# modul_frequency.net
KiCad netlist of a schematic drawn in EAGLE
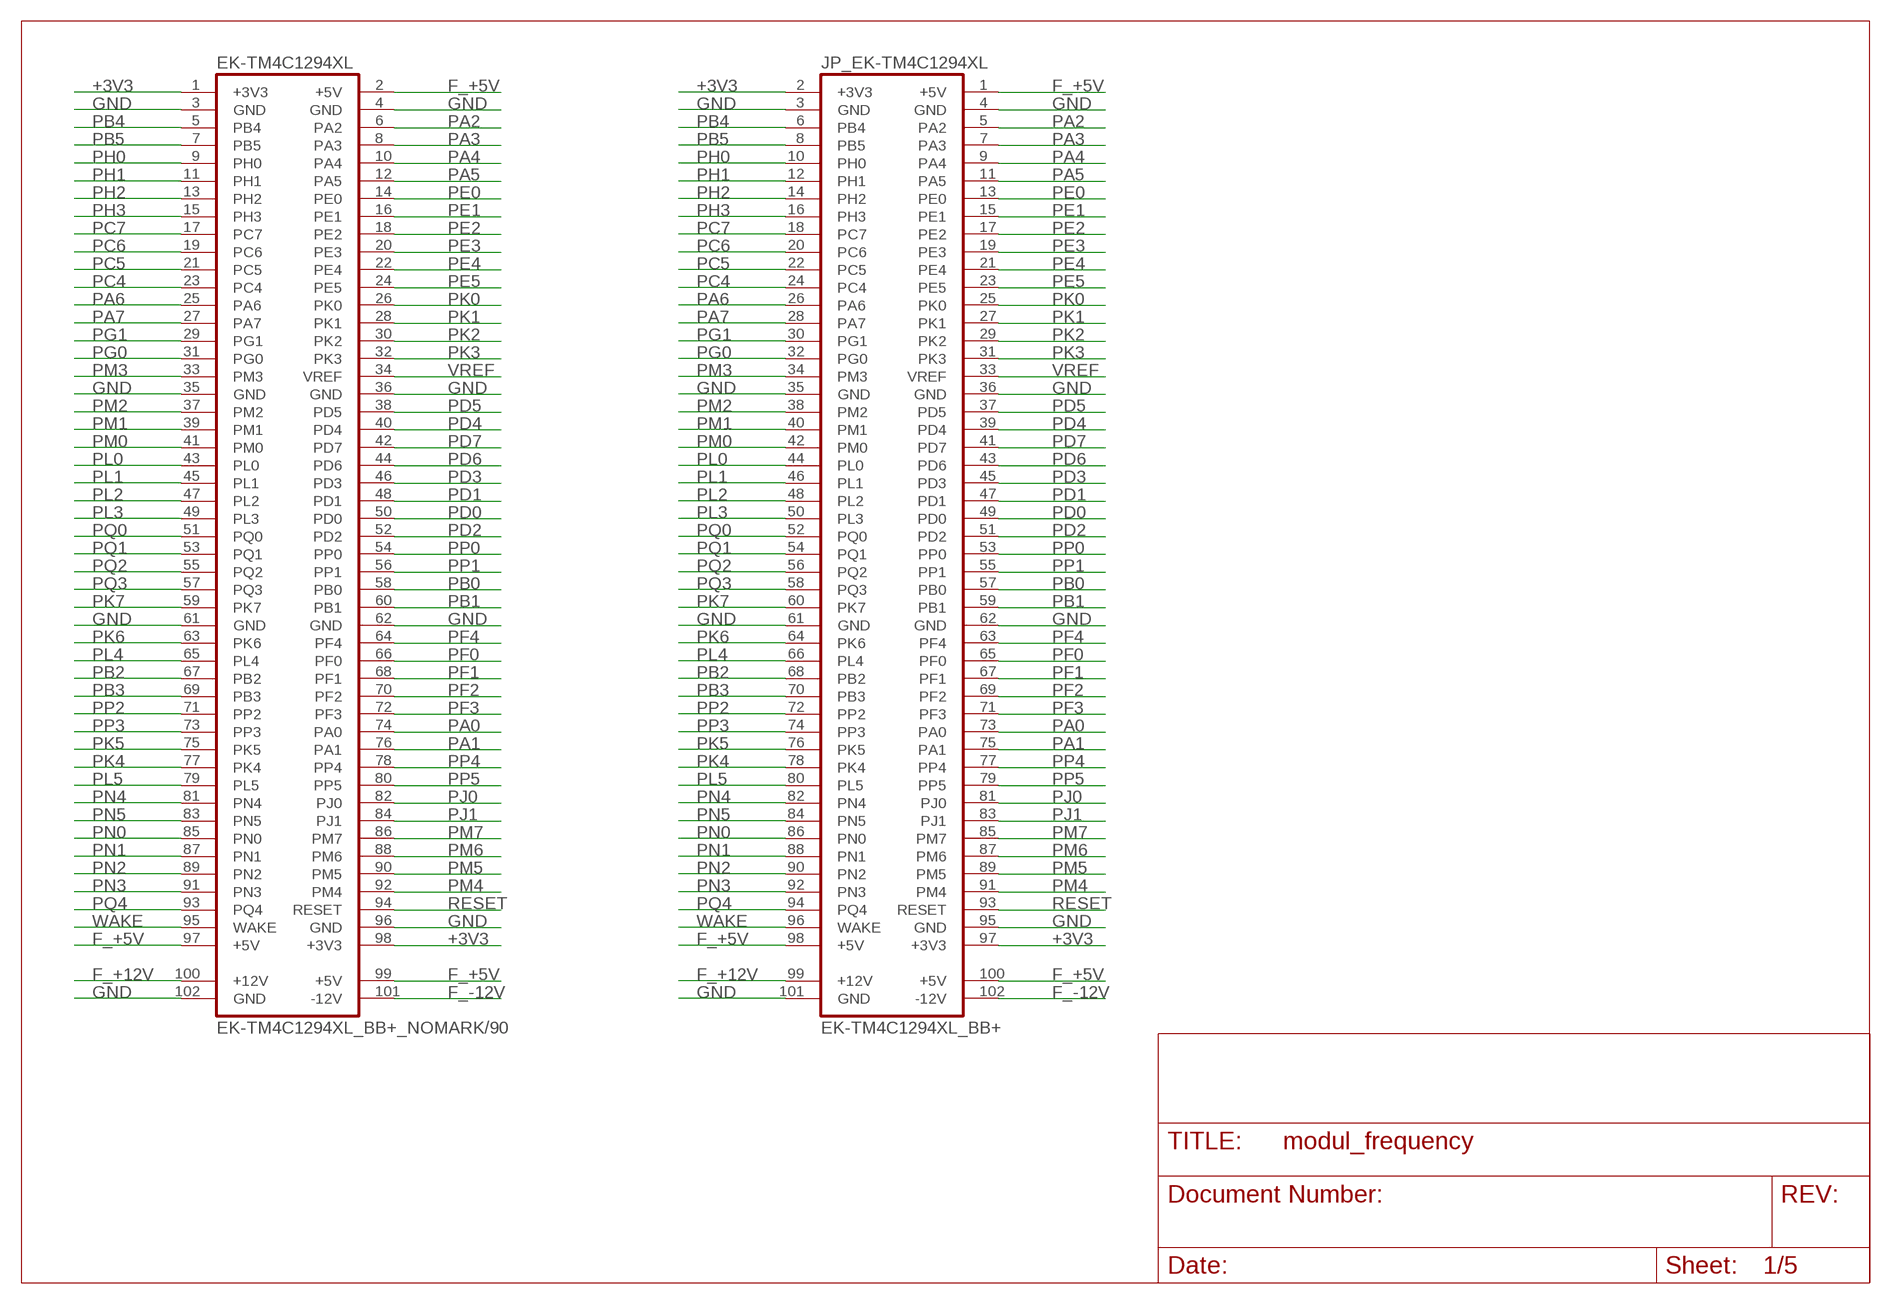
[diagram p0: schematic, sheet 1]
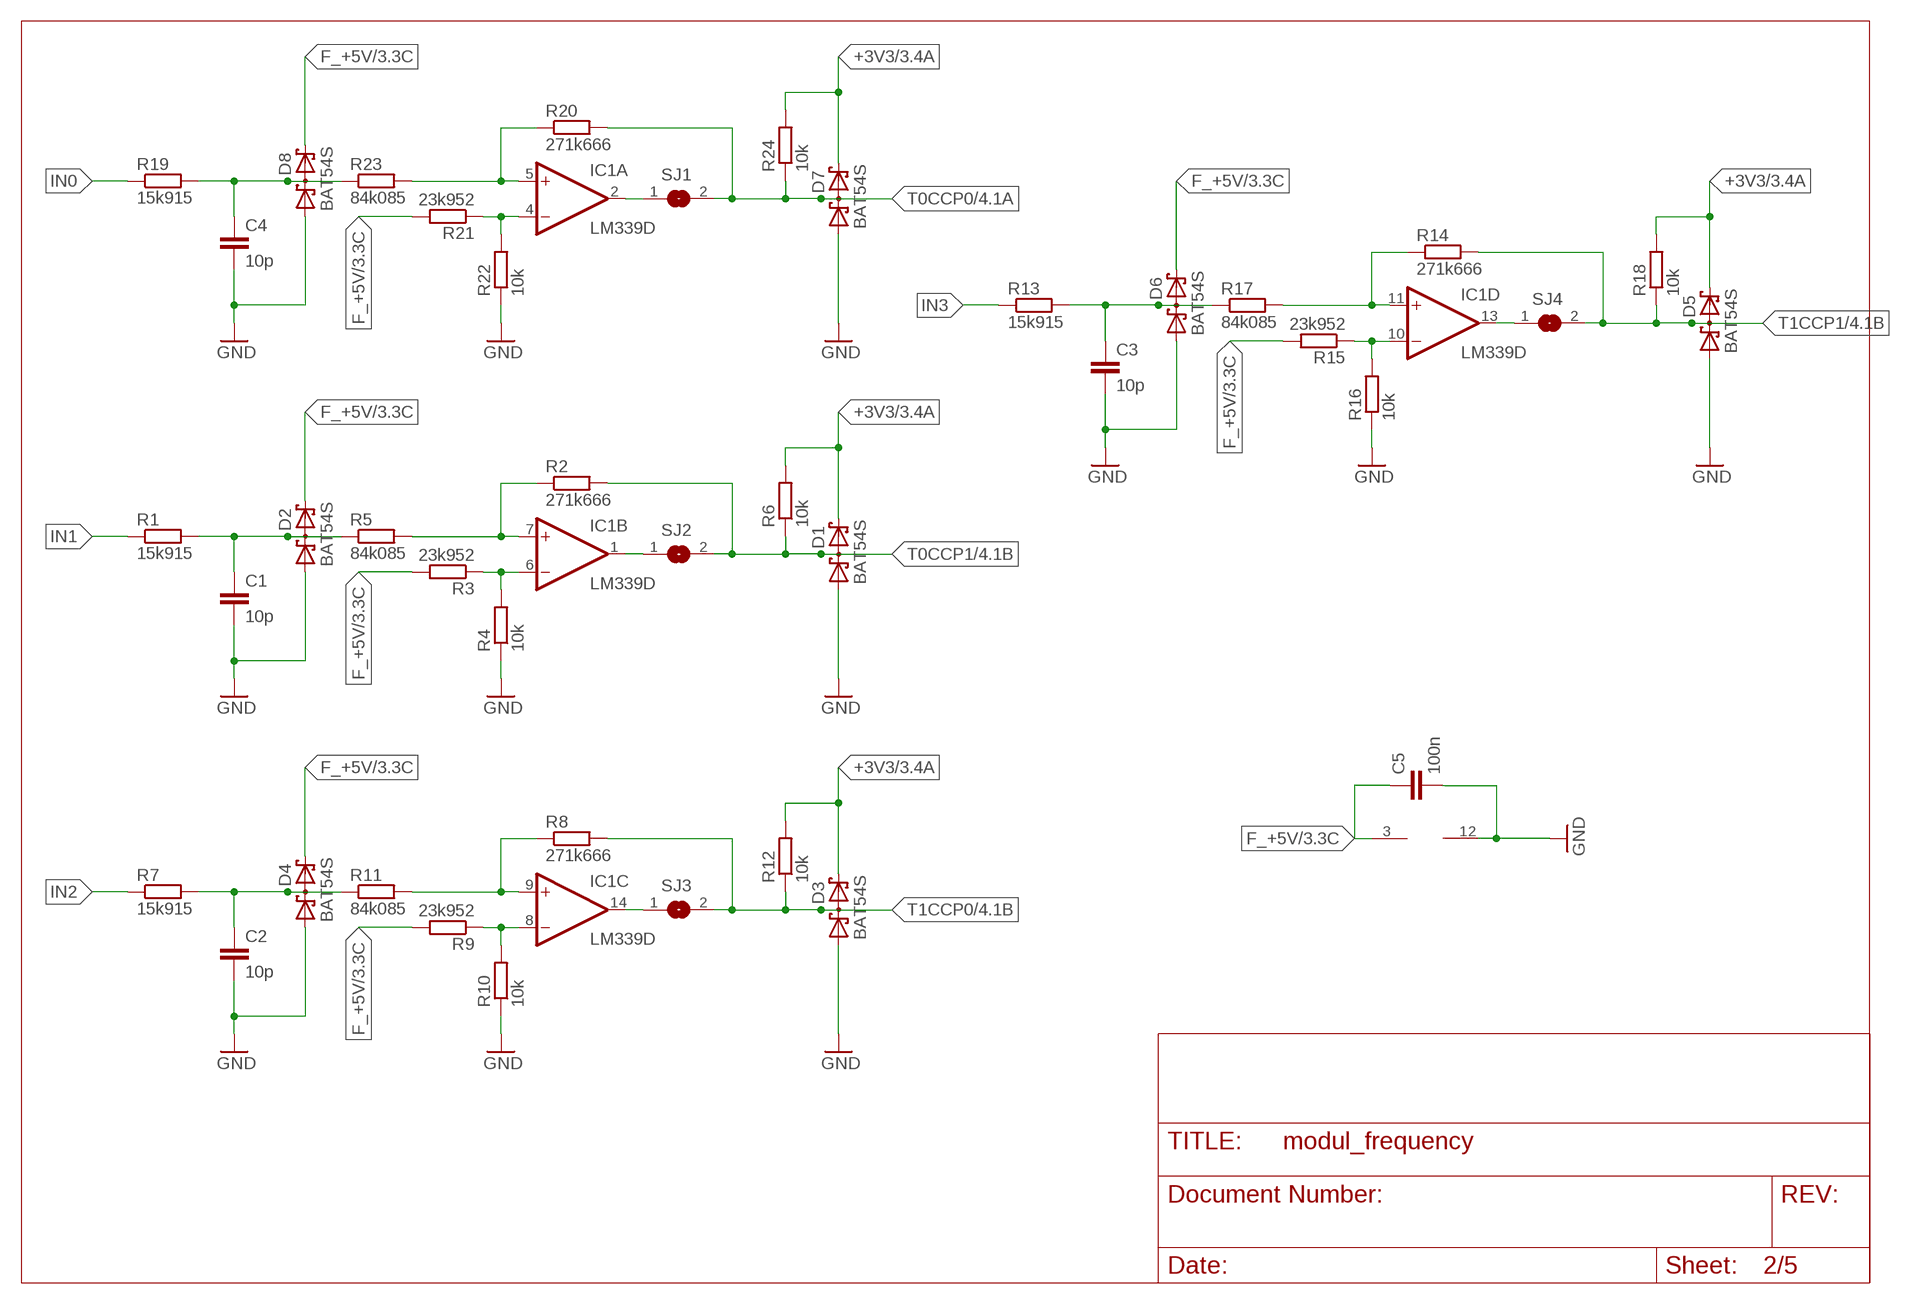
[diagram p1: schematic, sheet 2]
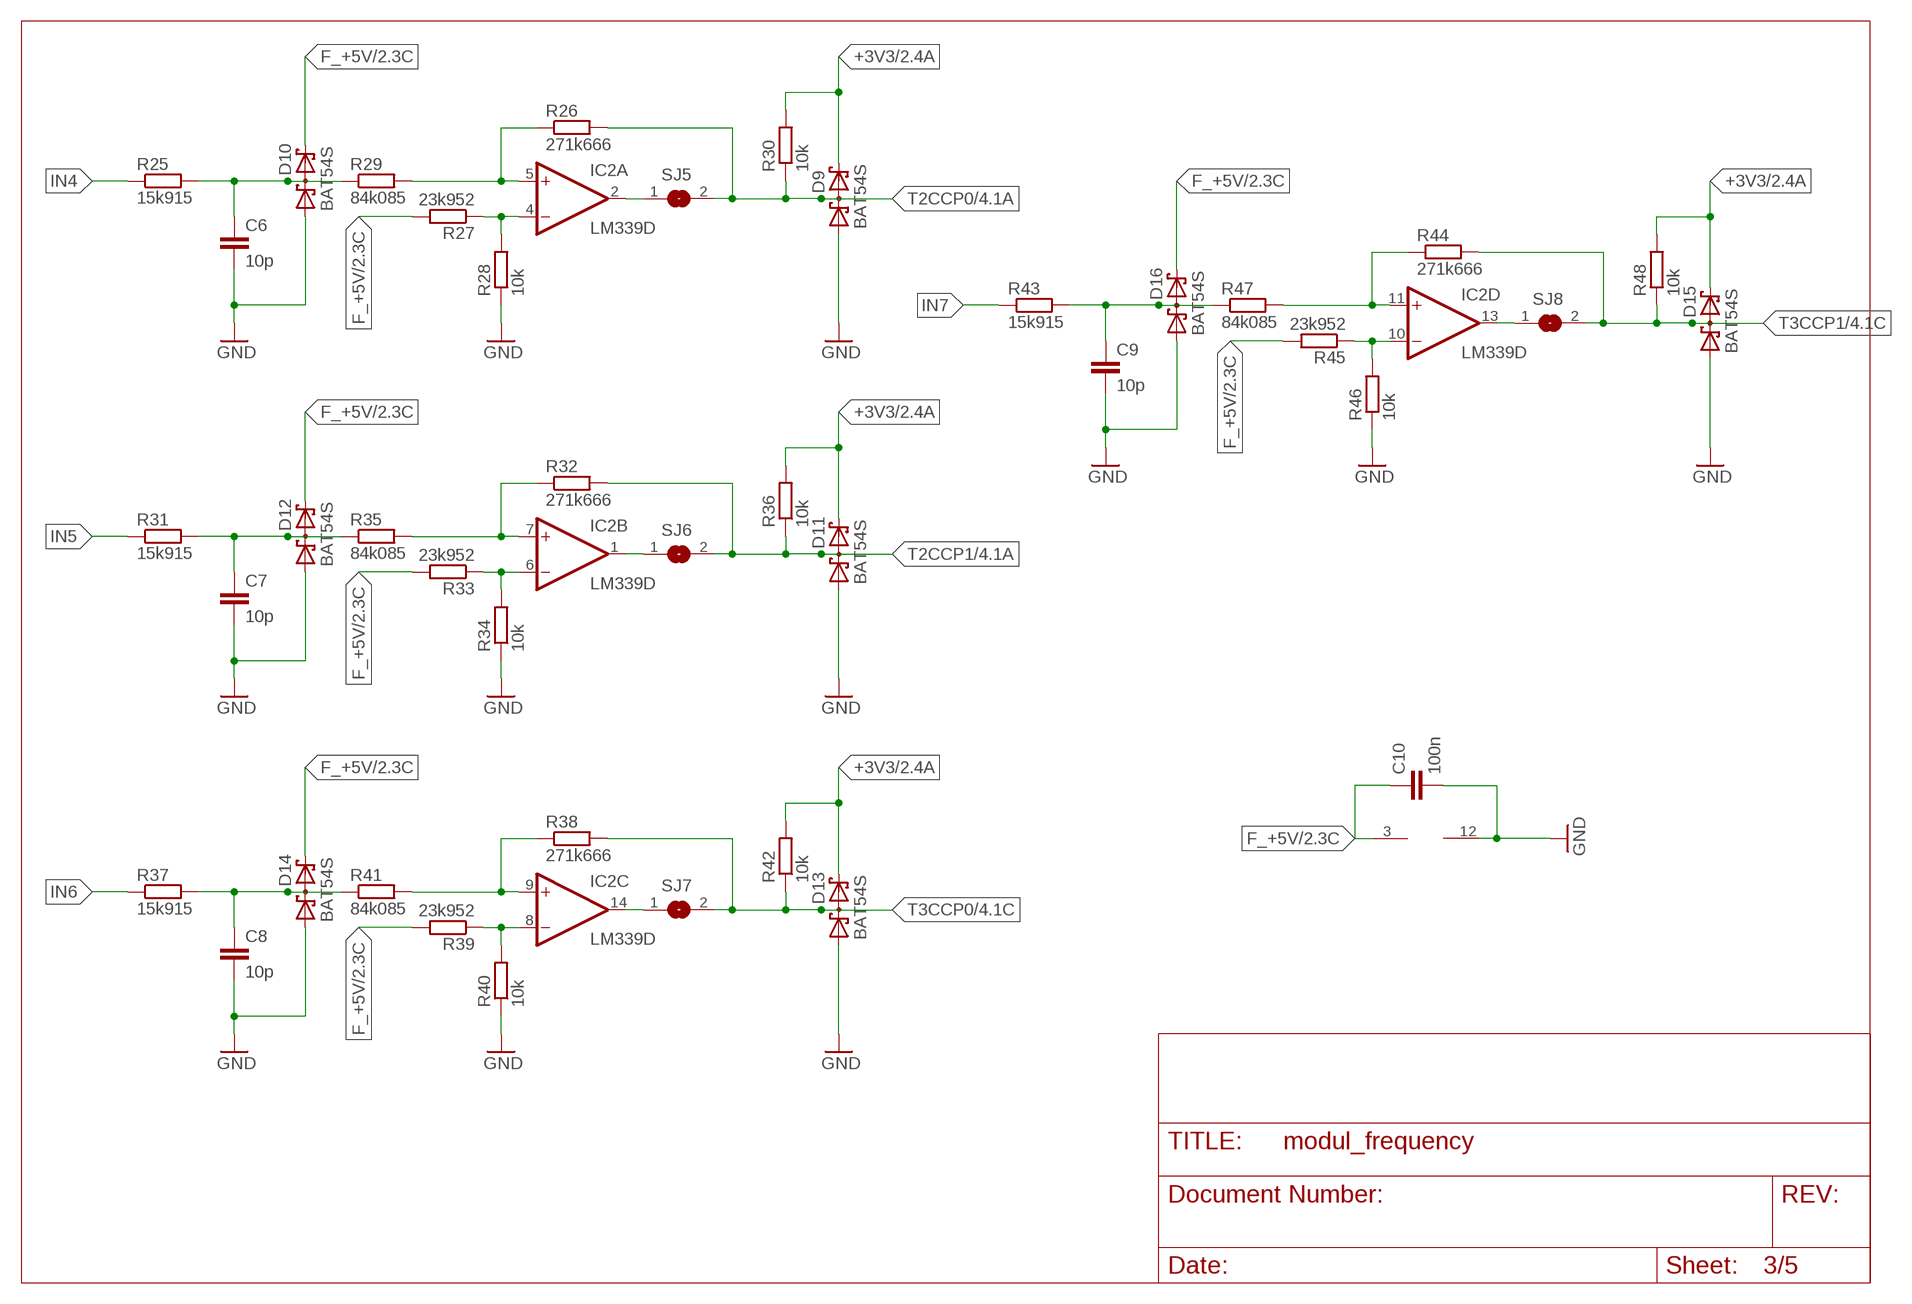
[diagram p2: schematic, sheet 3]
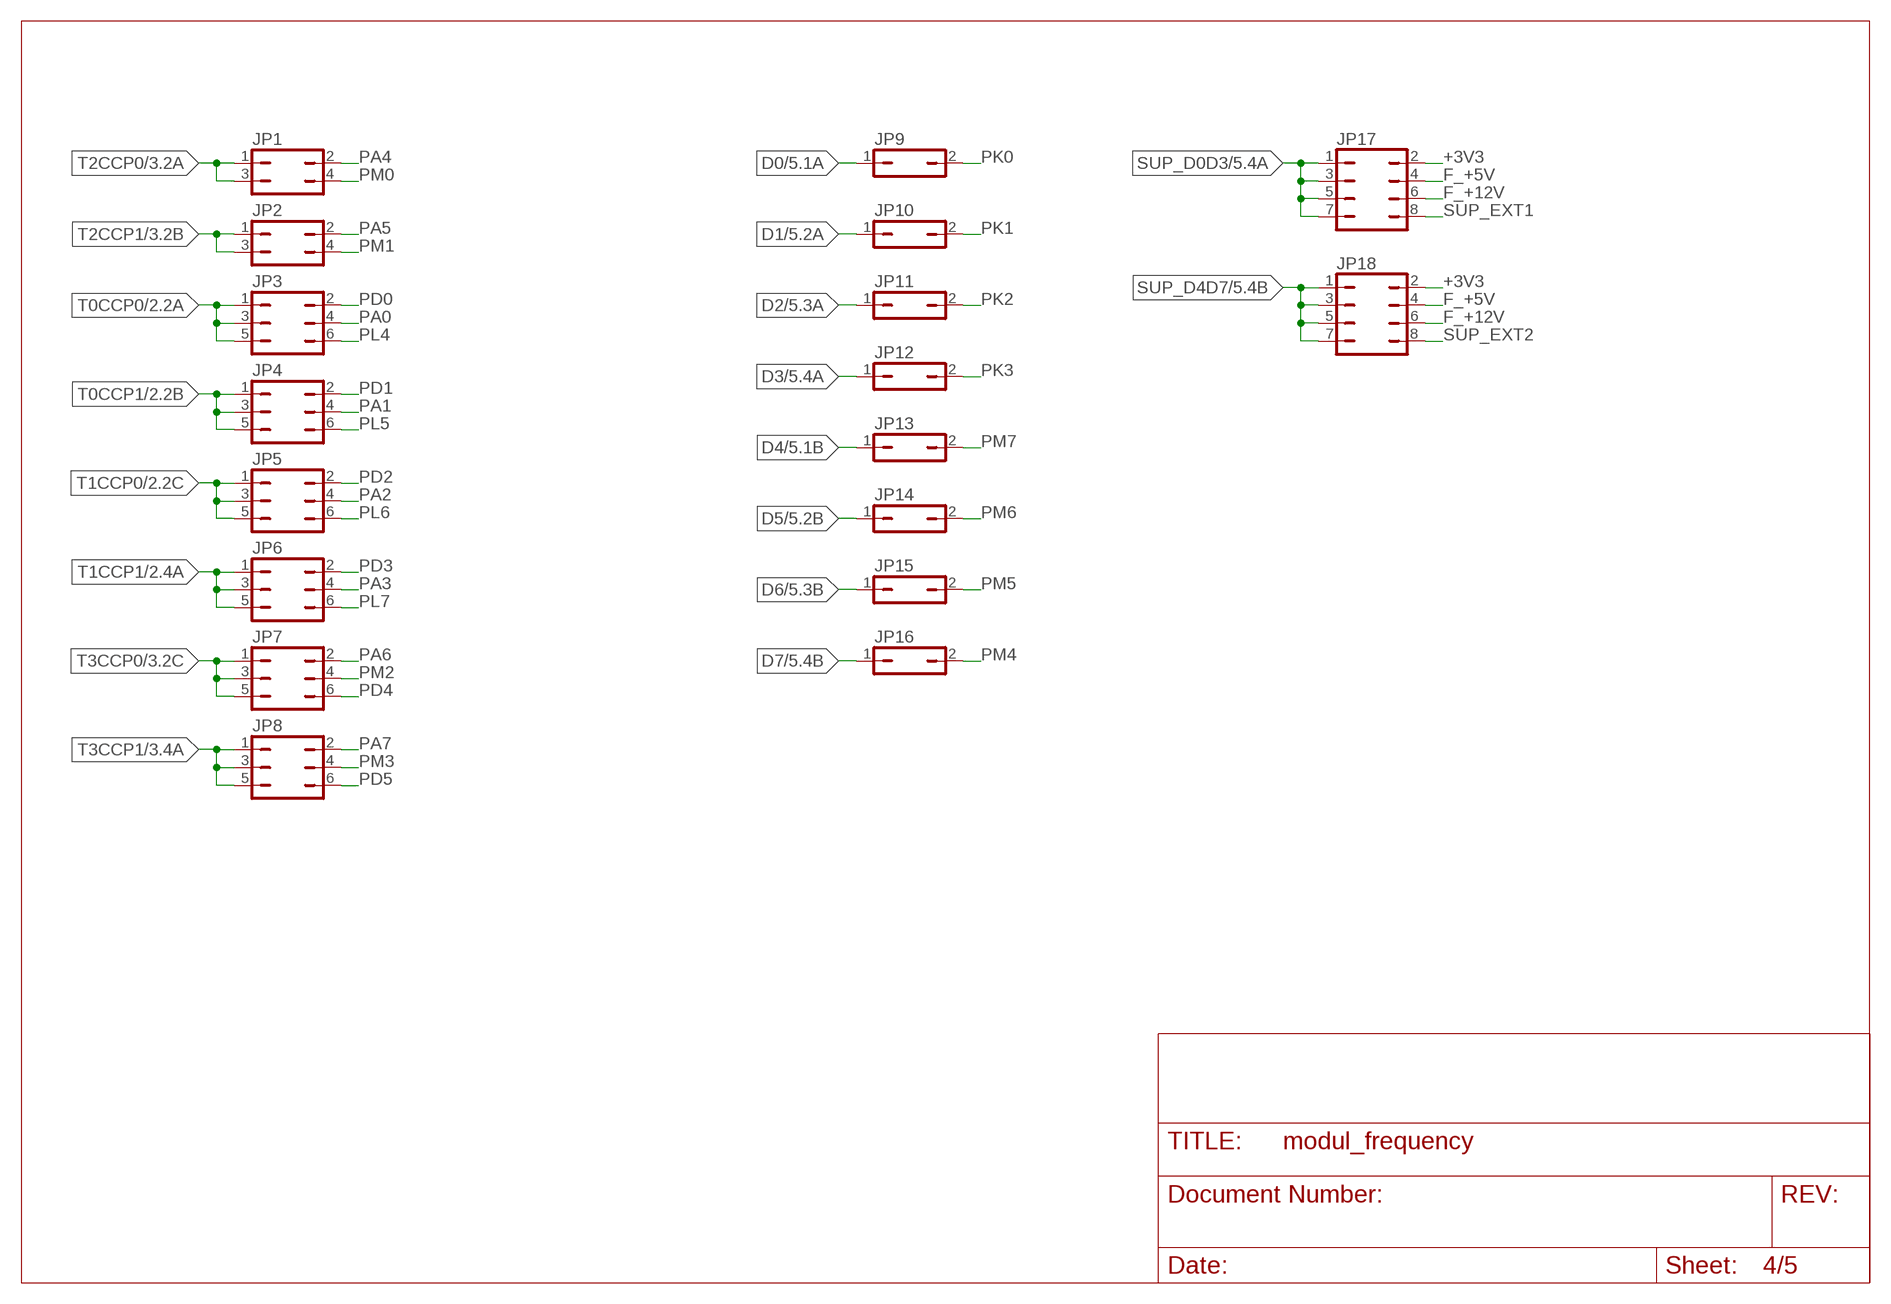
[diagram p3: schematic, sheet 4]
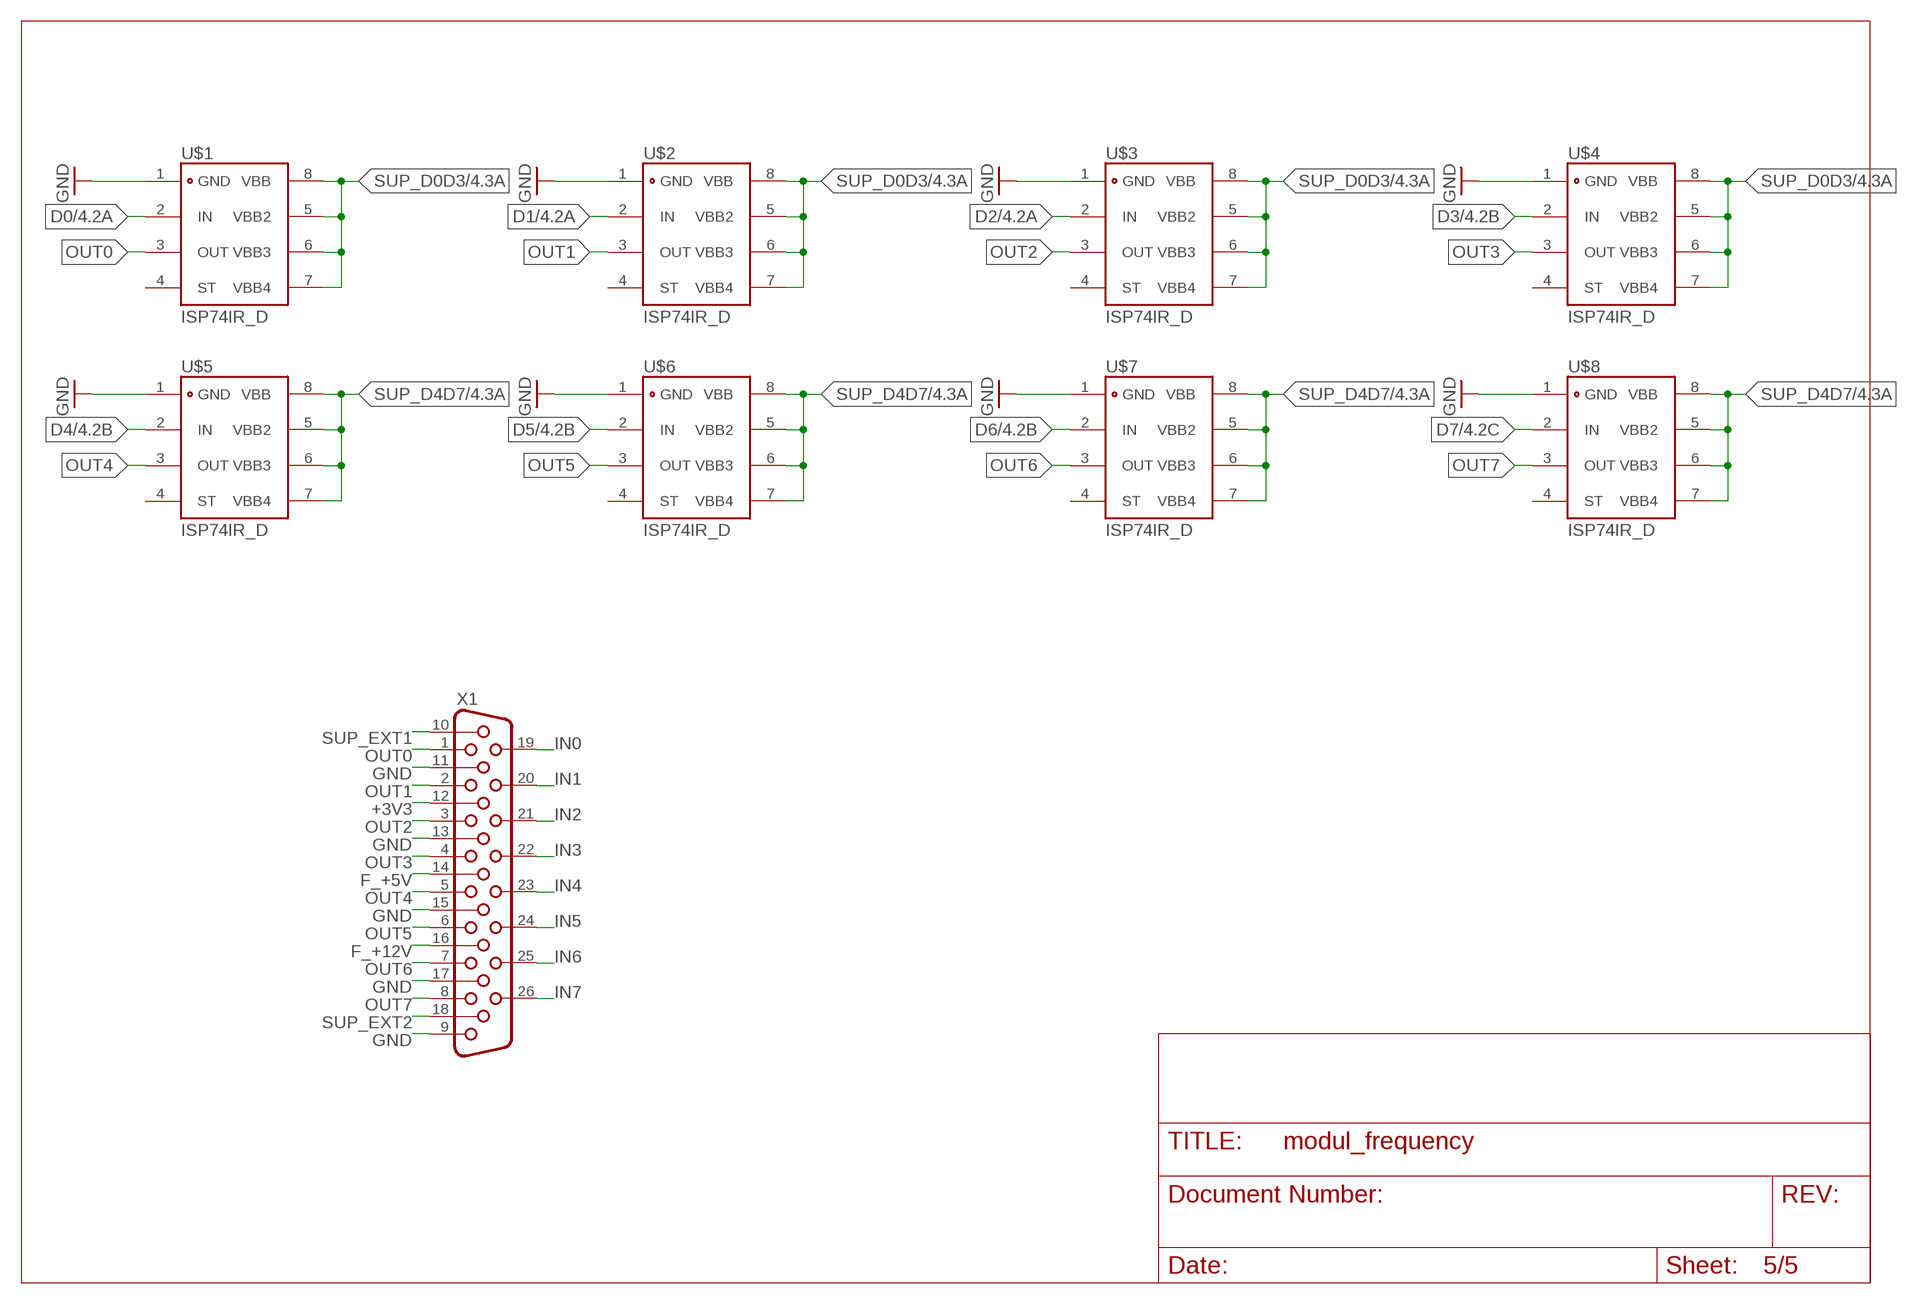
[diagram p4: schematic, sheet 5]

(export (version "E")
  (design (tool "Eeschema 10.0.6"))
  (components
    (comp (ref "EK-TM4C1294XL")
      (value "EK-TM4C1294XL_BB+_NOMARK/90")
      (footprint "eagle-import:EK-TM4C1294XL_BB+_NOMARK_90")
      (libsource (lib "eagle-import") (part "EK-TM4C1294XL_BB+_NOMARK/90"))
    )
    (comp (ref "JP_EK-TM4C1294XL")
      (value "EK-TM4C1294XL_BB+")
      (footprint "eagle-import:EK-TM4C1294XL_BB+")
      (libsource (lib "eagle-import") (part "EK-TM4C1294XL_BB+"))
    )
    (comp (ref "C6")
      (value "10p")
      (footprint "eagle-import:C0805")
      (libsource (lib "eagle-import") (part "C-EUC0805"))
    )
    (comp (ref "C7")
      (value "10p")
      (footprint "eagle-import:C0805")
      (libsource (lib "eagle-import") (part "C-EUC0805"))
    )
    (comp (ref "C8")
      (value "10p")
      (footprint "eagle-import:C0805")
      (libsource (lib "eagle-import") (part "C-EUC0805"))
    )
    (comp (ref "C9")
      (value "10p")
      (footprint "eagle-import:C0805")
      (libsource (lib "eagle-import") (part "C-EUC0805"))
    )
    (comp (ref "C10")
      (value "100n")
      (footprint "eagle-import:C0805")
      (libsource (lib "eagle-import") (part "C-EUC0805"))
    )
    (comp (ref "D9")
      (value "BAT54S")
      (footprint "eagle-import:SOT23")
      (libsource (lib "eagle-import") (part "BAT54S"))
    )
    (comp (ref "D10")
      (value "BAT54S")
      (footprint "eagle-import:SOT23")
      (libsource (lib "eagle-import") (part "BAT54S"))
    )
    (comp (ref "D11")
      (value "BAT54S")
      (footprint "eagle-import:SOT23")
      (libsource (lib "eagle-import") (part "BAT54S"))
    )
    (comp (ref "D12")
      (value "BAT54S")
      (footprint "eagle-import:SOT23")
      (libsource (lib "eagle-import") (part "BAT54S"))
    )
    (comp (ref "D13")
      (value "BAT54S")
      (footprint "eagle-import:SOT23")
      (libsource (lib "eagle-import") (part "BAT54S"))
    )
    (comp (ref "D14")
      (value "BAT54S")
      (footprint "eagle-import:SOT23")
      (libsource (lib "eagle-import") (part "BAT54S"))
    )
    (comp (ref "D15")
      (value "BAT54S")
      (footprint "eagle-import:SOT23")
      (libsource (lib "eagle-import") (part "BAT54S"))
    )
    (comp (ref "D16")
      (value "BAT54S")
      (footprint "eagle-import:SOT23")
      (libsource (lib "eagle-import") (part "BAT54S"))
    )
    (comp (ref "IC2")
      (value "LM339D")
      (footprint "eagle-import:SO14")
      (libsource (lib "eagle-import") (part "LM339D"))
    )
    (comp (ref "R25")
      (value "15k915")
      (footprint "eagle-import:R0805")
      (libsource (lib "eagle-import") (part "R-EU_R0805"))
    )
    (comp (ref "R26")
      (value "271k666")
      (footprint "eagle-import:R0805")
      (libsource (lib "eagle-import") (part "R-EU_R0805"))
    )
    (comp (ref "R27")
      (value "23k952")
      (footprint "eagle-import:R0805")
      (libsource (lib "eagle-import") (part "R-EU_R0805"))
    )
    (comp (ref "R28")
      (value "10k")
      (footprint "eagle-import:R0805")
      (libsource (lib "eagle-import") (part "R-EU_R0805"))
    )
    (comp (ref "R29")
      (value "84k085")
      (footprint "eagle-import:R0805")
      (libsource (lib "eagle-import") (part "R-EU_R0805"))
    )
    (comp (ref "R30")
      (value "10k")
      (footprint "eagle-import:R0805")
      (libsource (lib "eagle-import") (part "R-EU_R0805"))
    )
    (comp (ref "R31")
      (value "15k915")
      (footprint "eagle-import:R0805")
      (libsource (lib "eagle-import") (part "R-EU_R0805"))
    )
    (comp (ref "R32")
      (value "271k666")
      (footprint "eagle-import:R0805")
      (libsource (lib "eagle-import") (part "R-EU_R0805"))
    )
    (comp (ref "R33")
      (value "23k952")
      (footprint "eagle-import:R0805")
      (libsource (lib "eagle-import") (part "R-EU_R0805"))
    )
    (comp (ref "R34")
      (value "10k")
      (footprint "eagle-import:R0805")
      (libsource (lib "eagle-import") (part "R-EU_R0805"))
    )
    (comp (ref "R35")
      (value "84k085")
      (footprint "eagle-import:R0805")
      (libsource (lib "eagle-import") (part "R-EU_R0805"))
    )
    (comp (ref "R36")
      (value "10k")
      (footprint "eagle-import:R0805")
      (libsource (lib "eagle-import") (part "R-EU_R0805"))
    )
    (comp (ref "R37")
      (value "15k915")
      (footprint "eagle-import:R0805")
      (libsource (lib "eagle-import") (part "R-EU_R0805"))
    )
    (comp (ref "R38")
      (value "271k666")
      (footprint "eagle-import:R0805")
      (libsource (lib "eagle-import") (part "R-EU_R0805"))
    )
    (comp (ref "R39")
      (value "23k952")
      (footprint "eagle-import:R0805")
      (libsource (lib "eagle-import") (part "R-EU_R0805"))
    )
    (comp (ref "R40")
      (value "10k")
      (footprint "eagle-import:R0805")
      (libsource (lib "eagle-import") (part "R-EU_R0805"))
    )
    (comp (ref "R41")
      (value "84k085")
      (footprint "eagle-import:R0805")
      (libsource (lib "eagle-import") (part "R-EU_R0805"))
    )
    (comp (ref "R42")
      (value "10k")
      (footprint "eagle-import:R0805")
      (libsource (lib "eagle-import") (part "R-EU_R0805"))
    )
    (comp (ref "R43")
      (value "15k915")
      (footprint "eagle-import:R0805")
      (libsource (lib "eagle-import") (part "R-EU_R0805"))
    )
    (comp (ref "R44")
      (value "271k666")
      (footprint "eagle-import:R0805")
      (libsource (lib "eagle-import") (part "R-EU_R0805"))
    )
    (comp (ref "R45")
      (value "23k952")
      (footprint "eagle-import:R0805")
      (libsource (lib "eagle-import") (part "R-EU_R0805"))
    )
    (comp (ref "R46")
      (value "10k")
      (footprint "eagle-import:R0805")
      (libsource (lib "eagle-import") (part "R-EU_R0805"))
    )
    (comp (ref "R47")
      (value "84k085")
      (footprint "eagle-import:R0805")
      (libsource (lib "eagle-import") (part "R-EU_R0805"))
    )
    (comp (ref "R48")
      (value "10k")
      (footprint "eagle-import:R0805")
      (libsource (lib "eagle-import") (part "R-EU_R0805"))
    )
    (comp (ref "SJ5") (value "SJ") (footprint "eagle-import:SJ") (libsource (lib "eagle-import") (part "SJ")))
    (comp (ref "SJ6") (value "SJ") (footprint "eagle-import:SJ") (libsource (lib "eagle-import") (part "SJ")))
    (comp (ref "SJ7") (value "SJ") (footprint "eagle-import:SJ") (libsource (lib "eagle-import") (part "SJ")))
    (comp (ref "SJ8") (value "SJ") (footprint "eagle-import:SJ") (libsource (lib "eagle-import") (part "SJ")))
    (comp (ref "C1")
      (value "10p")
      (footprint "eagle-import:C0805")
      (libsource (lib "eagle-import") (part "C-EUC0805"))
    )
    (comp (ref "C2")
      (value "10p")
      (footprint "eagle-import:C0805")
      (libsource (lib "eagle-import") (part "C-EUC0805"))
    )
    (comp (ref "C3")
      (value "10p")
      (footprint "eagle-import:C0805")
      (libsource (lib "eagle-import") (part "C-EUC0805"))
    )
    (comp (ref "C4")
      (value "10p")
      (footprint "eagle-import:C0805")
      (libsource (lib "eagle-import") (part "C-EUC0805"))
    )
    (comp (ref "C5")
      (value "100n")
      (footprint "eagle-import:C0805")
      (libsource (lib "eagle-import") (part "C-EUC0805"))
    )
    (comp (ref "D1")
      (value "BAT54S")
      (footprint "eagle-import:SOT23")
      (libsource (lib "eagle-import") (part "BAT54S"))
    )
    (comp (ref "D2")
      (value "BAT54S")
      (footprint "eagle-import:SOT23")
      (libsource (lib "eagle-import") (part "BAT54S"))
    )
    (comp (ref "D3")
      (value "BAT54S")
      (footprint "eagle-import:SOT23")
      (libsource (lib "eagle-import") (part "BAT54S"))
    )
    (comp (ref "D4")
      (value "BAT54S")
      (footprint "eagle-import:SOT23")
      (libsource (lib "eagle-import") (part "BAT54S"))
    )
    (comp (ref "D5")
      (value "BAT54S")
      (footprint "eagle-import:SOT23")
      (libsource (lib "eagle-import") (part "BAT54S"))
    )
    (comp (ref "D6")
      (value "BAT54S")
      (footprint "eagle-import:SOT23")
      (libsource (lib "eagle-import") (part "BAT54S"))
    )
    (comp (ref "D7")
      (value "BAT54S")
      (footprint "eagle-import:SOT23")
      (libsource (lib "eagle-import") (part "BAT54S"))
    )
    (comp (ref "D8")
      (value "BAT54S")
      (footprint "eagle-import:SOT23")
      (libsource (lib "eagle-import") (part "BAT54S"))
    )
    (comp (ref "IC1")
      (value "LM339D")
      (footprint "eagle-import:SO14")
      (libsource (lib "eagle-import") (part "LM339D"))
    )
    (comp (ref "R1")
      (value "15k915")
      (footprint "eagle-import:R0805")
      (libsource (lib "eagle-import") (part "R-EU_R0805"))
    )
    (comp (ref "R2")
      (value "271k666")
      (footprint "eagle-import:R0805")
      (libsource (lib "eagle-import") (part "R-EU_R0805"))
    )
    (comp (ref "R3")
      (value "23k952")
      (footprint "eagle-import:R0805")
      (libsource (lib "eagle-import") (part "R-EU_R0805"))
    )
    (comp (ref "R4")
      (value "10k")
      (footprint "eagle-import:R0805")
      (libsource (lib "eagle-import") (part "R-EU_R0805"))
    )
    (comp (ref "R5")
      (value "84k085")
      (footprint "eagle-import:R0805")
      (libsource (lib "eagle-import") (part "R-EU_R0805"))
    )
    (comp (ref "R6")
      (value "10k")
      (footprint "eagle-import:R0805")
      (libsource (lib "eagle-import") (part "R-EU_R0805"))
    )
    (comp (ref "R7")
      (value "15k915")
      (footprint "eagle-import:R0805")
      (libsource (lib "eagle-import") (part "R-EU_R0805"))
    )
    (comp (ref "R8")
      (value "271k666")
      (footprint "eagle-import:R0805")
      (libsource (lib "eagle-import") (part "R-EU_R0805"))
    )
    (comp (ref "R9")
      (value "23k952")
      (footprint "eagle-import:R0805")
      (libsource (lib "eagle-import") (part "R-EU_R0805"))
    )
    (comp (ref "R10")
      (value "10k")
      (footprint "eagle-import:R0805")
      (libsource (lib "eagle-import") (part "R-EU_R0805"))
    )
    (comp (ref "R11")
      (value "84k085")
      (footprint "eagle-import:R0805")
      (libsource (lib "eagle-import") (part "R-EU_R0805"))
    )
    (comp (ref "R12")
      (value "10k")
      (footprint "eagle-import:R0805")
      (libsource (lib "eagle-import") (part "R-EU_R0805"))
    )
    (comp (ref "R13")
      (value "15k915")
      (footprint "eagle-import:R0805")
      (libsource (lib "eagle-import") (part "R-EU_R0805"))
    )
    (comp (ref "R14")
      (value "271k666")
      (footprint "eagle-import:R0805")
      (libsource (lib "eagle-import") (part "R-EU_R0805"))
    )
    (comp (ref "R15")
      (value "23k952")
      (footprint "eagle-import:R0805")
      (libsource (lib "eagle-import") (part "R-EU_R0805"))
    )
    (comp (ref "R16")
      (value "10k")
      (footprint "eagle-import:R0805")
      (libsource (lib "eagle-import") (part "R-EU_R0805"))
    )
    (comp (ref "R17")
      (value "84k085")
      (footprint "eagle-import:R0805")
      (libsource (lib "eagle-import") (part "R-EU_R0805"))
    )
    (comp (ref "R18")
      (value "10k")
      (footprint "eagle-import:R0805")
      (libsource (lib "eagle-import") (part "R-EU_R0805"))
    )
    (comp (ref "R19")
      (value "15k915")
      (footprint "eagle-import:R0805")
      (libsource (lib "eagle-import") (part "R-EU_R0805"))
    )
    (comp (ref "R20")
      (value "271k666")
      (footprint "eagle-import:R0805")
      (libsource (lib "eagle-import") (part "R-EU_R0805"))
    )
    (comp (ref "R21")
      (value "23k952")
      (footprint "eagle-import:R0805")
      (libsource (lib "eagle-import") (part "R-EU_R0805"))
    )
    (comp (ref "R22")
      (value "10k")
      (footprint "eagle-import:R0805")
      (libsource (lib "eagle-import") (part "R-EU_R0805"))
    )
    (comp (ref "R23")
      (value "84k085")
      (footprint "eagle-import:R0805")
      (libsource (lib "eagle-import") (part "R-EU_R0805"))
    )
    (comp (ref "R24")
      (value "10k")
      (footprint "eagle-import:R0805")
      (libsource (lib "eagle-import") (part "R-EU_R0805"))
    )
    (comp (ref "SJ1") (value "SJ") (footprint "eagle-import:SJ") (libsource (lib "eagle-import") (part "SJ")))
    (comp (ref "SJ2") (value "SJ") (footprint "eagle-import:SJ") (libsource (lib "eagle-import") (part "SJ")))
    (comp (ref "SJ3") (value "SJ") (footprint "eagle-import:SJ") (libsource (lib "eagle-import") (part "SJ")))
    (comp (ref "SJ4") (value "SJ") (footprint "eagle-import:SJ") (libsource (lib "eagle-import") (part "SJ")))
    (comp (ref "U$1")
      (value "ISP74IR_D")
      (footprint "eagle-import:SO08")
      (libsource (lib "eagle-import") (part "ISP74IR_D"))
    )
    (comp (ref "U$2")
      (value "ISP74IR_D")
      (footprint "eagle-import:SO08")
      (libsource (lib "eagle-import") (part "ISP74IR_D"))
    )
    (comp (ref "U$3")
      (value "ISP74IR_D")
      (footprint "eagle-import:SO08")
      (libsource (lib "eagle-import") (part "ISP74IR_D"))
    )
    (comp (ref "U$4")
      (value "ISP74IR_D")
      (footprint "eagle-import:SO08")
      (libsource (lib "eagle-import") (part "ISP74IR_D"))
    )
    (comp (ref "U$5")
      (value "ISP74IR_D")
      (footprint "eagle-import:SO08")
      (libsource (lib "eagle-import") (part "ISP74IR_D"))
    )
    (comp (ref "U$6")
      (value "ISP74IR_D")
      (footprint "eagle-import:SO08")
      (libsource (lib "eagle-import") (part "ISP74IR_D"))
    )
    (comp (ref "U$7")
      (value "ISP74IR_D")
      (footprint "eagle-import:SO08")
      (libsource (lib "eagle-import") (part "ISP74IR_D"))
    )
    (comp (ref "U$8")
      (value "ISP74IR_D")
      (footprint "eagle-import:SO08")
      (libsource (lib "eagle-import") (part "ISP74IR_D"))
    )
    (comp (ref "X1")
      (value "HF26H")
      (footprint "eagle-import:HDF26H")
      (libsource (lib "eagle-import") (part "HF26H"))
    )
    (comp (ref "JP1")
      (value "JP2Q")
      (footprint "eagle-import:JP2Q")
      (libsource (lib "eagle-import") (part "JP2Q"))
    )
    (comp (ref "JP2")
      (value "JP2Q")
      (footprint "eagle-import:JP2Q")
      (libsource (lib "eagle-import") (part "JP2Q"))
    )
    (comp (ref "JP3")
      (value "JP3Q")
      (footprint "eagle-import:JP3Q")
      (libsource (lib "eagle-import") (part "JP3Q"))
    )
    (comp (ref "JP4")
      (value "JP3Q")
      (footprint "eagle-import:JP3Q")
      (libsource (lib "eagle-import") (part "JP3Q"))
    )
    (comp (ref "JP5")
      (value "JP3Q")
      (footprint "eagle-import:JP3Q")
      (libsource (lib "eagle-import") (part "JP3Q"))
    )
    (comp (ref "JP6")
      (value "JP3Q")
      (footprint "eagle-import:JP3Q")
      (libsource (lib "eagle-import") (part "JP3Q"))
    )
    (comp (ref "JP7")
      (value "JP3Q")
      (footprint "eagle-import:JP3Q")
      (libsource (lib "eagle-import") (part "JP3Q"))
    )
    (comp (ref "JP8")
      (value "JP3Q")
      (footprint "eagle-import:JP3Q")
      (libsource (lib "eagle-import") (part "JP3Q"))
    )
    (comp (ref "JP9")
      (value "JP1Q")
      (footprint "eagle-import:JP1")
      (libsource (lib "eagle-import") (part "JP1Q"))
    )
    (comp (ref "JP10")
      (value "JP1Q")
      (footprint "eagle-import:JP1")
      (libsource (lib "eagle-import") (part "JP1Q"))
    )
    (comp (ref "JP11")
      (value "JP1Q")
      (footprint "eagle-import:JP1")
      (libsource (lib "eagle-import") (part "JP1Q"))
    )
    (comp (ref "JP12")
      (value "JP1Q")
      (footprint "eagle-import:JP1")
      (libsource (lib "eagle-import") (part "JP1Q"))
    )
    (comp (ref "JP13")
      (value "JP1Q")
      (footprint "eagle-import:JP1")
      (libsource (lib "eagle-import") (part "JP1Q"))
    )
    (comp (ref "JP14")
      (value "JP1Q")
      (footprint "eagle-import:JP1")
      (libsource (lib "eagle-import") (part "JP1Q"))
    )
    (comp (ref "JP15")
      (value "JP1Q")
      (footprint "eagle-import:JP1")
      (libsource (lib "eagle-import") (part "JP1Q"))
    )
    (comp (ref "JP16")
      (value "JP1Q")
      (footprint "eagle-import:JP1")
      (libsource (lib "eagle-import") (part "JP1Q"))
    )
    (comp (ref "JP17")
      (value "JP4Q")
      (footprint "eagle-import:JP4Q")
      (libsource (lib "eagle-import") (part "JP4Q"))
    )
    (comp (ref "JP18")
      (value "JP4Q")
      (footprint "eagle-import:JP4Q")
      (libsource (lib "eagle-import") (part "JP4Q"))
    )
  )
  (nets
    (net (code "1") (name "+3V3") (class "Default")
      (node (ref "D1") (pin "2") (pinfunction "C2_2") (pintype "passive"))
      (node (ref "D11") (pin "2") (pinfunction "C2_2") (pintype "passive"))
      (node (ref "D13") (pin "2") (pinfunction "C2_2") (pintype "passive"))
      (node (ref "D15") (pin "2") (pinfunction "C2_2") (pintype "passive"))
      (node (ref "D3") (pin "2") (pinfunction "C2_2") (pintype "passive"))
      (node (ref "D5") (pin "2") (pinfunction "C2_2") (pintype "passive"))
      (node (ref "D7") (pin "2") (pinfunction "C2_2") (pintype "passive"))
      (node (ref "D9") (pin "2") (pinfunction "C2_2") (pintype "passive"))
      (node (ref "EK-TM4C1294XL") (pin "1") (pinfunction "+3V3_1") (pintype "power_in"))
      (node (ref "EK-TM4C1294XL") (pin "98") (pinfunction "+3V3_98") (pintype "power_in"))
      (node (ref "JP17") (pin "2") (pinfunction "2_2") (pintype "passive"))
      (node (ref "JP18") (pin "2") (pinfunction "2_2") (pintype "passive"))
      (node (ref "JP_EK-TM4C1294XL") (pin "2") (pinfunction "+3V3_2") (pintype "power_in"))
      (node (ref "JP_EK-TM4C1294XL") (pin "97") (pinfunction "+3V3_97") (pintype "power_in"))
      (node (ref "R12") (pin "2") (pinfunction "2_2") (pintype "passive"))
      (node (ref "R18") (pin "2") (pinfunction "2_2") (pintype "passive"))
      (node (ref "R24") (pin "2") (pinfunction "2_2") (pintype "passive"))
      (node (ref "R30") (pin "2") (pinfunction "2_2") (pintype "passive"))
      (node (ref "R36") (pin "2") (pinfunction "2_2") (pintype "passive"))
      (node (ref "R42") (pin "2") (pinfunction "2_2") (pintype "passive"))
      (node (ref "R48") (pin "2") (pinfunction "2_2") (pintype "passive"))
      (node (ref "R6") (pin "2") (pinfunction "2_2") (pintype "passive"))
      (node (ref "X1") (pin "12") (pinfunction "12_12") (pintype "passive"))
    )
    (net (code "2") (name "D0") (class "Default")
      (node (ref "JP9") (pin "1") (pinfunction "1_1") (pintype "passive"))
      (node (ref "U$1") (pin "2") (pinfunction "IN_2") (pintype "bidirectional"))
    )
    (net (code "3") (name "D1") (class "Default")
      (node (ref "JP10") (pin "1") (pinfunction "1_1") (pintype "passive"))
      (node (ref "U$2") (pin "2") (pinfunction "IN_2") (pintype "bidirectional"))
    )
    (net (code "4") (name "D2") (class "Default")
      (node (ref "JP11") (pin "1") (pinfunction "1_1") (pintype "passive"))
      (node (ref "U$3") (pin "2") (pinfunction "IN_2") (pintype "bidirectional"))
    )
    (net (code "5") (name "D3") (class "Default")
      (node (ref "JP12") (pin "1") (pinfunction "1_1") (pintype "passive"))
      (node (ref "U$4") (pin "2") (pinfunction "IN_2") (pintype "bidirectional"))
    )
    (net (code "6") (name "D4") (class "Default")
      (node (ref "JP13") (pin "1") (pinfunction "1_1") (pintype "passive"))
      (node (ref "U$5") (pin "2") (pinfunction "IN_2") (pintype "bidirectional"))
    )
    (net (code "7") (name "D5") (class "Default")
      (node (ref "JP14") (pin "1") (pinfunction "1_1") (pintype "passive"))
      (node (ref "U$6") (pin "2") (pinfunction "IN_2") (pintype "bidirectional"))
    )
    (net (code "8") (name "D6") (class "Default")
      (node (ref "JP15") (pin "1") (pinfunction "1_1") (pintype "passive"))
      (node (ref "U$7") (pin "2") (pinfunction "IN_2") (pintype "bidirectional"))
    )
    (net (code "9") (name "D7") (class "Default")
      (node (ref "JP16") (pin "1") (pinfunction "1_1") (pintype "passive"))
      (node (ref "U$8") (pin "2") (pinfunction "IN_2") (pintype "bidirectional"))
    )
    (net (code "10") (name "F_+5V") (class "Default")
      (node (ref "C10") (pin "1") (pinfunction "1_1") (pintype "passive"))
      (node (ref "C5") (pin "1") (pinfunction "1_1") (pintype "passive"))
      (node (ref "D10") (pin "2") (pinfunction "C2_2") (pintype "passive"))
      (node (ref "D12") (pin "2") (pinfunction "C2_2") (pintype "passive"))
      (node (ref "D14") (pin "2") (pinfunction "C2_2") (pintype "passive"))
      (node (ref "D16") (pin "2") (pinfunction "C2_2") (pintype "passive"))
      (node (ref "D2") (pin "2") (pinfunction "C2_2") (pintype "passive"))
      (node (ref "D4") (pin "2") (pinfunction "C2_2") (pintype "passive"))
      (node (ref "D6") (pin "2") (pinfunction "C2_2") (pintype "passive"))
      (node (ref "D8") (pin "2") (pinfunction "C2_2") (pintype "passive"))
      (node (ref "EK-TM4C1294XL") (pin "2") (pinfunction "+5V_2") (pintype "power_in"))
      (node (ref "EK-TM4C1294XL") (pin "97") (pinfunction "+5V_97") (pintype "power_in"))
      (node (ref "EK-TM4C1294XL") (pin "99") (pinfunction "+5V_99") (pintype "power_in"))
      (node (ref "IC1") (pin "3") (pinfunction "V+_3") (pintype "power_in"))
      (node (ref "IC2") (pin "3") (pinfunction "V+_3") (pintype "power_in"))
      (node (ref "JP17") (pin "4") (pinfunction "4_4") (pintype "passive"))
      (node (ref "JP18") (pin "4") (pinfunction "4_4") (pintype "passive"))
      (node (ref "JP_EK-TM4C1294XL") (pin "1") (pinfunction "+5V_1") (pintype "power_in"))
      (node (ref "JP_EK-TM4C1294XL") (pin "100") (pinfunction "+5V_100") (pintype "power_in"))
      (node (ref "JP_EK-TM4C1294XL") (pin "98") (pinfunction "+5V_98") (pintype "power_in"))
      (node (ref "R15") (pin "2") (pinfunction "2_2") (pintype "passive"))
      (node (ref "R21") (pin "2") (pinfunction "2_2") (pintype "passive"))
      (node (ref "R27") (pin "2") (pinfunction "2_2") (pintype "passive"))
      (node (ref "R3") (pin "2") (pinfunction "2_2") (pintype "passive"))
      (node (ref "R33") (pin "2") (pinfunction "2_2") (pintype "passive"))
      (node (ref "R39") (pin "2") (pinfunction "2_2") (pintype "passive"))
      (node (ref "R45") (pin "2") (pinfunction "2_2") (pintype "passive"))
      (node (ref "R9") (pin "2") (pinfunction "2_2") (pintype "passive"))
      (node (ref "X1") (pin "14") (pinfunction "14_14") (pintype "passive"))
    )
    (net (code "11") (name "F_+12V") (class "Default")
      (node (ref "EK-TM4C1294XL") (pin "100") (pinfunction "+12V_100") (pintype "power_in"))
      (node (ref "JP17") (pin "6") (pinfunction "6_6") (pintype "passive"))
      (node (ref "JP18") (pin "6") (pinfunction "6_6") (pintype "passive"))
      (node (ref "JP_EK-TM4C1294XL") (pin "99") (pinfunction "+12V_99") (pintype "power_in"))
      (node (ref "X1") (pin "16") (pinfunction "16_16") (pintype "passive"))
    )
    (net (code "12") (name "F_-12V") (class "Default")
      (node (ref "EK-TM4C1294XL") (pin "101") (pinfunction "-12V_101") (pintype "power_in"))
      (node (ref "JP_EK-TM4C1294XL") (pin "102") (pinfunction "-12V_102") (pintype "power_in"))
    )
    (net (code "13") (name "GND") (class "Default")
      (node (ref "C1") (pin "2") (pinfunction "2_2") (pintype "passive"))
      (node (ref "C10") (pin "2") (pinfunction "2_2") (pintype "passive"))
      (node (ref "C2") (pin "2") (pinfunction "2_2") (pintype "passive"))
      (node (ref "C3") (pin "2") (pinfunction "2_2") (pintype "passive"))
      (node (ref "C4") (pin "2") (pinfunction "2_2") (pintype "passive"))
      (node (ref "C5") (pin "2") (pinfunction "2_2") (pintype "passive"))
      (node (ref "C6") (pin "2") (pinfunction "2_2") (pintype "passive"))
      (node (ref "C7") (pin "2") (pinfunction "2_2") (pintype "passive"))
      (node (ref "C8") (pin "2") (pinfunction "2_2") (pintype "passive"))
      (node (ref "C9") (pin "2") (pinfunction "2_2") (pintype "passive"))
      (node (ref "D1") (pin "1") (pinfunction "A1_1") (pintype "passive"))
      (node (ref "D10") (pin "1") (pinfunction "A1_1") (pintype "passive"))
      (node (ref "D11") (pin "1") (pinfunction "A1_1") (pintype "passive"))
      (node (ref "D12") (pin "1") (pinfunction "A1_1") (pintype "passive"))
      (node (ref "D13") (pin "1") (pinfunction "A1_1") (pintype "passive"))
      (node (ref "D14") (pin "1") (pinfunction "A1_1") (pintype "passive"))
      (node (ref "D15") (pin "1") (pinfunction "A1_1") (pintype "passive"))
      (node (ref "D16") (pin "1") (pinfunction "A1_1") (pintype "passive"))
      (node (ref "D2") (pin "1") (pinfunction "A1_1") (pintype "passive"))
      (node (ref "D3") (pin "1") (pinfunction "A1_1") (pintype "passive"))
      (node (ref "D4") (pin "1") (pinfunction "A1_1") (pintype "passive"))
      (node (ref "D5") (pin "1") (pinfunction "A1_1") (pintype "passive"))
      (node (ref "D6") (pin "1") (pinfunction "A1_1") (pintype "passive"))
      (node (ref "D7") (pin "1") (pinfunction "A1_1") (pintype "passive"))
      (node (ref "D8") (pin "1") (pinfunction "A1_1") (pintype "passive"))
      (node (ref "D9") (pin "1") (pinfunction "A1_1") (pintype "passive"))
      (node (ref "EK-TM4C1294XL") (pin "102") (pinfunction "GND_102") (pintype "power_in"))
      (node (ref "EK-TM4C1294XL") (pin "3") (pinfunction "GND_3") (pintype "power_in"))
      (node (ref "EK-TM4C1294XL") (pin "35") (pinfunction "GND_35") (pintype "power_in"))
      (node (ref "EK-TM4C1294XL") (pin "36") (pinfunction "GND_36") (pintype "power_in"))
      (node (ref "EK-TM4C1294XL") (pin "4") (pinfunction "GND_4") (pintype "power_in"))
      (node (ref "EK-TM4C1294XL") (pin "61") (pinfunction "GND_61") (pintype "power_in"))
      (node (ref "EK-TM4C1294XL") (pin "62") (pinfunction "GND_62") (pintype "power_in"))
      (node (ref "EK-TM4C1294XL") (pin "96") (pinfunction "GND_96") (pintype "power_in"))
      (node (ref "IC1") (pin "12") (pinfunction "GND_12") (pintype "power_in"))
      (node (ref "IC2") (pin "12") (pinfunction "GND_12") (pintype "power_in"))
      (node (ref "JP_EK-TM4C1294XL") (pin "101") (pinfunction "GND_101") (pintype "power_in"))
      (node (ref "JP_EK-TM4C1294XL") (pin "3") (pinfunction "GND_3") (pintype "power_in"))
      (node (ref "JP_EK-TM4C1294XL") (pin "35") (pinfunction "GND_35") (pintype "power_in"))
      (node (ref "JP_EK-TM4C1294XL") (pin "36") (pinfunction "GND_36") (pintype "power_in"))
      (node (ref "JP_EK-TM4C1294XL") (pin "4") (pinfunction "GND_4") (pintype "power_in"))
      (node (ref "JP_EK-TM4C1294XL") (pin "61") (pinfunction "GND_61") (pintype "power_in"))
      (node (ref "JP_EK-TM4C1294XL") (pin "62") (pinfunction "GND_62") (pintype "power_in"))
      (node (ref "JP_EK-TM4C1294XL") (pin "95") (pinfunction "GND_95") (pintype "power_in"))
      (node (ref "R10") (pin "1") (pinfunction "1_1") (pintype "passive"))
      (node (ref "R16") (pin "1") (pinfunction "1_1") (pintype "passive"))
      (node (ref "R22") (pin "1") (pinfunction "1_1") (pintype "passive"))
      (node (ref "R28") (pin "1") (pinfunction "1_1") (pintype "passive"))
      (node (ref "R34") (pin "1") (pinfunction "1_1") (pintype "passive"))
      (node (ref "R4") (pin "1") (pinfunction "1_1") (pintype "passive"))
      (node (ref "R40") (pin "1") (pinfunction "1_1") (pintype "passive"))
      (node (ref "R46") (pin "1") (pinfunction "1_1") (pintype "passive"))
      (node (ref "U$1") (pin "1") (pinfunction "GND_1") (pintype "bidirectional"))
      (node (ref "U$2") (pin "1") (pinfunction "GND_1") (pintype "bidirectional"))
      (node (ref "U$3") (pin "1") (pinfunction "GND_1") (pintype "bidirectional"))
      (node (ref "U$4") (pin "1") (pinfunction "GND_1") (pintype "bidirectional"))
      (node (ref "U$5") (pin "1") (pinfunction "GND_1") (pintype "bidirectional"))
      (node (ref "U$6") (pin "1") (pinfunction "GND_1") (pintype "bidirectional"))
      (node (ref "U$7") (pin "1") (pinfunction "GND_1") (pintype "bidirectional"))
      (node (ref "U$8") (pin "1") (pinfunction "GND_1") (pintype "bidirectional"))
      (node (ref "X1") (pin "11") (pinfunction "11_11") (pintype "passive"))
      (node (ref "X1") (pin "13") (pinfunction "13_13") (pintype "passive"))
      (node (ref "X1") (pin "15") (pinfunction "15_15") (pintype "passive"))
      (node (ref "X1") (pin "17") (pinfunction "17_17") (pintype "passive"))
      (node (ref "X1") (pin "9") (pinfunction "9_9") (pintype "passive"))
    )
    (net (code "14") (name "IN0") (class "Default")
      (node (ref "R19") (pin "1") (pinfunction "1_1") (pintype "passive"))
      (node (ref "X1") (pin "19") (pinfunction "19_19") (pintype "passive"))
    )
    (net (code "15") (name "IN1") (class "Default")
      (node (ref "R1") (pin "1") (pinfunction "1_1") (pintype "passive"))
      (node (ref "X1") (pin "20") (pinfunction "20_20") (pintype "passive"))
    )
    (net (code "16") (name "IN2") (class "Default")
      (node (ref "R7") (pin "1") (pinfunction "1_1") (pintype "passive"))
      (node (ref "X1") (pin "21") (pinfunction "21_21") (pintype "passive"))
    )
    (net (code "17") (name "IN3") (class "Default")
      (node (ref "R13") (pin "1") (pinfunction "1_1") (pintype "passive"))
      (node (ref "X1") (pin "22") (pinfunction "22_22") (pintype "passive"))
    )
    (net (code "18") (name "IN4") (class "Default")
      (node (ref "R25") (pin "1") (pinfunction "1_1") (pintype "passive"))
      (node (ref "X1") (pin "23") (pinfunction "23_23") (pintype "passive"))
    )
    (net (code "19") (name "IN5") (class "Default")
      (node (ref "R31") (pin "1") (pinfunction "1_1") (pintype "passive"))
      (node (ref "X1") (pin "24") (pinfunction "24_24") (pintype "passive"))
    )
    (net (code "20") (name "IN6") (class "Default")
      (node (ref "R37") (pin "1") (pinfunction "1_1") (pintype "passive"))
      (node (ref "X1") (pin "25") (pinfunction "25_25") (pintype "passive"))
    )
    (net (code "21") (name "IN7") (class "Default")
      (node (ref "R43") (pin "1") (pinfunction "1_1") (pintype "passive"))
      (node (ref "X1") (pin "26") (pinfunction "26_26") (pintype "passive"))
    )
    (net (code "22") (name "Net-(D2-C1A2)") (class "Default")
      (node (ref "C1") (pin "1") (pinfunction "1_1") (pintype "passive"))
      (node (ref "D2") (pin "3") (pinfunction "C1A2_3") (pintype "passive"))
      (node (ref "R1") (pin "2") (pinfunction "2_2") (pintype "passive"))
      (node (ref "R5") (pin "1") (pinfunction "1_1") (pintype "passive"))
    )
    (net (code "23") (name "Net-(D4-C1A2)") (class "Default")
      (node (ref "C2") (pin "1") (pinfunction "1_1") (pintype "passive"))
      (node (ref "D4") (pin "3") (pinfunction "C1A2_3") (pintype "passive"))
      (node (ref "R11") (pin "1") (pinfunction "1_1") (pintype "passive"))
      (node (ref "R7") (pin "2") (pinfunction "2_2") (pintype "passive"))
    )
    (net (code "24") (name "Net-(D6-C1A2)") (class "Default")
      (node (ref "C3") (pin "1") (pinfunction "1_1") (pintype "passive"))
      (node (ref "D6") (pin "3") (pinfunction "C1A2_3") (pintype "passive"))
      (node (ref "R13") (pin "2") (pinfunction "2_2") (pintype "passive"))
      (node (ref "R17") (pin "1") (pinfunction "1_1") (pintype "passive"))
    )
    (net (code "25") (name "Net-(D8-C1A2)") (class "Default")
      (node (ref "C4") (pin "1") (pinfunction "1_1") (pintype "passive"))
      (node (ref "D8") (pin "3") (pinfunction "C1A2_3") (pintype "passive"))
      (node (ref "R19") (pin "2") (pinfunction "2_2") (pintype "passive"))
      (node (ref "R23") (pin "1") (pinfunction "1_1") (pintype "passive"))
    )
    (net (code "26") (name "Net-(D10-C1A2)") (class "Default")
      (node (ref "C6") (pin "1") (pinfunction "1_1") (pintype "passive"))
      (node (ref "D10") (pin "3") (pinfunction "C1A2_3") (pintype "passive"))
      (node (ref "R25") (pin "2") (pinfunction "2_2") (pintype "passive"))
      (node (ref "R29") (pin "1") (pinfunction "1_1") (pintype "passive"))
    )
    (net (code "27") (name "Net-(D12-C1A2)") (class "Default")
      (node (ref "C7") (pin "1") (pinfunction "1_1") (pintype "passive"))
      (node (ref "D12") (pin "3") (pinfunction "C1A2_3") (pintype "passive"))
      (node (ref "R31") (pin "2") (pinfunction "2_2") (pintype "passive"))
      (node (ref "R35") (pin "1") (pinfunction "1_1") (pintype "passive"))
    )
    (net (code "28") (name "Net-(D14-C1A2)") (class "Default")
      (node (ref "C8") (pin "1") (pinfunction "1_1") (pintype "passive"))
      (node (ref "D14") (pin "3") (pinfunction "C1A2_3") (pintype "passive"))
      (node (ref "R37") (pin "2") (pinfunction "2_2") (pintype "passive"))
      (node (ref "R41") (pin "1") (pinfunction "1_1") (pintype "passive"))
    )
    (net (code "29") (name "Net-(D16-C1A2)") (class "Default")
      (node (ref "C9") (pin "1") (pinfunction "1_1") (pintype "passive"))
      (node (ref "D16") (pin "3") (pinfunction "C1A2_3") (pintype "passive"))
      (node (ref "R43") (pin "2") (pinfunction "2_2") (pintype "passive"))
      (node (ref "R47") (pin "1") (pinfunction "1_1") (pintype "passive"))
    )
    (net (code "30") (name "Net-(IC1A-+IN)") (class "Default")
      (node (ref "IC1") (pin "5") (pinfunction "+IN_5") (pintype "input"))
      (node (ref "R20") (pin "1") (pinfunction "1_1") (pintype "passive"))
      (node (ref "R23") (pin "2") (pinfunction "2_2") (pintype "passive"))
    )
    (net (code "31") (name "Net-(IC1A--IN)") (class "Default")
      (node (ref "IC1") (pin "4") (pinfunction "-IN_4") (pintype "input"))
      (node (ref "R21") (pin "1") (pinfunction "1_1") (pintype "passive"))
      (node (ref "R22") (pin "2") (pinfunction "2_2") (pintype "passive"))
    )
    (net (code "32") (name "Net-(IC1A-OUT)") (class "Default")
      (node (ref "IC1") (pin "2") (pinfunction "OUT_2") (pintype "open_collector"))
      (node (ref "SJ1") (pin "1") (pinfunction "1_1") (pintype "passive"))
    )
    (net (code "33") (name "Net-(IC1B-+IN)") (class "Default")
      (node (ref "IC1") (pin "7") (pinfunction "+IN_7") (pintype "input"))
      (node (ref "R2") (pin "1") (pinfunction "1_1") (pintype "passive"))
      (node (ref "R5") (pin "2") (pinfunction "2_2") (pintype "passive"))
    )
    (net (code "34") (name "Net-(IC1B--IN)") (class "Default")
      (node (ref "IC1") (pin "6") (pinfunction "-IN_6") (pintype "input"))
      (node (ref "R3") (pin "1") (pinfunction "1_1") (pintype "passive"))
      (node (ref "R4") (pin "2") (pinfunction "2_2") (pintype "passive"))
    )
    (net (code "35") (name "Net-(IC1B-OUT)") (class "Default")
      (node (ref "IC1") (pin "1") (pinfunction "OUT_1") (pintype "open_collector"))
      (node (ref "SJ2") (pin "1") (pinfunction "1_1") (pintype "passive"))
    )
    (net (code "36") (name "Net-(IC1C-+IN)") (class "Default")
      (node (ref "IC1") (pin "9") (pinfunction "+IN_9") (pintype "input"))
      (node (ref "R11") (pin "2") (pinfunction "2_2") (pintype "passive"))
      (node (ref "R8") (pin "1") (pinfunction "1_1") (pintype "passive"))
    )
    (net (code "37") (name "Net-(IC1C--IN)") (class "Default")
      (node (ref "IC1") (pin "8") (pinfunction "-IN_8") (pintype "input"))
      (node (ref "R10") (pin "2") (pinfunction "2_2") (pintype "passive"))
      (node (ref "R9") (pin "1") (pinfunction "1_1") (pintype "passive"))
    )
    (net (code "38") (name "Net-(IC1C-OUT)") (class "Default")
      (node (ref "IC1") (pin "14") (pinfunction "OUT_14") (pintype "open_collector"))
      (node (ref "SJ3") (pin "1") (pinfunction "1_1") (pintype "passive"))
    )
    (net (code "39") (name "Net-(IC1D-+IN)") (class "Default")
      (node (ref "IC1") (pin "11") (pinfunction "+IN_11") (pintype "input"))
      (node (ref "R14") (pin "1") (pinfunction "1_1") (pintype "passive"))
      (node (ref "R17") (pin "2") (pinfunction "2_2") (pintype "passive"))
    )
    (net (code "40") (name "Net-(IC1D--IN)") (class "Default")
      (node (ref "IC1") (pin "10") (pinfunction "-IN_10") (pintype "input"))
      (node (ref "R15") (pin "1") (pinfunction "1_1") (pintype "passive"))
      (node (ref "R16") (pin "2") (pinfunction "2_2") (pintype "passive"))
    )
    (net (code "41") (name "Net-(IC1D-OUT)") (class "Default")
      (node (ref "IC1") (pin "13") (pinfunction "OUT_13") (pintype "open_collector"))
      (node (ref "SJ4") (pin "1") (pinfunction "1_1") (pintype "passive"))
    )
    (net (code "42") (name "Net-(IC2A-+IN)") (class "Default")
      (node (ref "IC2") (pin "5") (pinfunction "+IN_5") (pintype "input"))
      (node (ref "R26") (pin "1") (pinfunction "1_1") (pintype "passive"))
      (node (ref "R29") (pin "2") (pinfunction "2_2") (pintype "passive"))
    )
    (net (code "43") (name "Net-(IC2A--IN)") (class "Default")
      (node (ref "IC2") (pin "4") (pinfunction "-IN_4") (pintype "input"))
      (node (ref "R27") (pin "1") (pinfunction "1_1") (pintype "passive"))
      (node (ref "R28") (pin "2") (pinfunction "2_2") (pintype "passive"))
    )
    (net (code "44") (name "Net-(IC2A-OUT)") (class "Default")
      (node (ref "IC2") (pin "2") (pinfunction "OUT_2") (pintype "open_collector"))
      (node (ref "SJ5") (pin "1") (pinfunction "1_1") (pintype "passive"))
    )
    (net (code "45") (name "Net-(IC2B-+IN)") (class "Default")
      (node (ref "IC2") (pin "7") (pinfunction "+IN_7") (pintype "input"))
      (node (ref "R32") (pin "1") (pinfunction "1_1") (pintype "passive"))
      (node (ref "R35") (pin "2") (pinfunction "2_2") (pintype "passive"))
    )
    (net (code "46") (name "Net-(IC2B--IN)") (class "Default")
      (node (ref "IC2") (pin "6") (pinfunction "-IN_6") (pintype "input"))
      (node (ref "R33") (pin "1") (pinfunction "1_1") (pintype "passive"))
      (node (ref "R34") (pin "2") (pinfunction "2_2") (pintype "passive"))
    )
    (net (code "47") (name "Net-(IC2B-OUT)") (class "Default")
      (node (ref "IC2") (pin "1") (pinfunction "OUT_1") (pintype "open_collector"))
      (node (ref "SJ6") (pin "1") (pinfunction "1_1") (pintype "passive"))
    )
    (net (code "48") (name "Net-(IC2C-+IN)") (class "Default")
      (node (ref "IC2") (pin "9") (pinfunction "+IN_9") (pintype "input"))
      (node (ref "R38") (pin "1") (pinfunction "1_1") (pintype "passive"))
      (node (ref "R41") (pin "2") (pinfunction "2_2") (pintype "passive"))
    )
    (net (code "49") (name "Net-(IC2C--IN)") (class "Default")
      (node (ref "IC2") (pin "8") (pinfunction "-IN_8") (pintype "input"))
      (node (ref "R39") (pin "1") (pinfunction "1_1") (pintype "passive"))
      (node (ref "R40") (pin "2") (pinfunction "2_2") (pintype "passive"))
    )
    (net (code "50") (name "Net-(IC2C-OUT)") (class "Default")
      (node (ref "IC2") (pin "14") (pinfunction "OUT_14") (pintype "open_collector"))
      (node (ref "SJ7") (pin "1") (pinfunction "1_1") (pintype "passive"))
    )
    (net (code "51") (name "Net-(IC2D-+IN)") (class "Default")
      (node (ref "IC2") (pin "11") (pinfunction "+IN_11") (pintype "input"))
      (node (ref "R44") (pin "1") (pinfunction "1_1") (pintype "passive"))
      (node (ref "R47") (pin "2") (pinfunction "2_2") (pintype "passive"))
    )
    (net (code "52") (name "Net-(IC2D--IN)") (class "Default")
      (node (ref "IC2") (pin "10") (pinfunction "-IN_10") (pintype "input"))
      (node (ref "R45") (pin "1") (pinfunction "1_1") (pintype "passive"))
      (node (ref "R46") (pin "2") (pinfunction "2_2") (pintype "passive"))
    )
    (net (code "53") (name "Net-(IC2D-OUT)") (class "Default")
      (node (ref "IC2") (pin "13") (pinfunction "OUT_13") (pintype "open_collector"))
      (node (ref "SJ8") (pin "1") (pinfunction "1_1") (pintype "passive"))
    )
    (net (code "54") (name "OUT0") (class "Default")
      (node (ref "U$1") (pin "3") (pinfunction "OUT_3") (pintype "bidirectional"))
      (node (ref "X1") (pin "1") (pinfunction "1_1") (pintype "passive"))
    )
    (net (code "55") (name "OUT1") (class "Default")
      (node (ref "U$2") (pin "3") (pinfunction "OUT_3") (pintype "bidirectional"))
      (node (ref "X1") (pin "2") (pinfunction "2_2") (pintype "passive"))
    )
    (net (code "56") (name "OUT2") (class "Default")
      (node (ref "U$3") (pin "3") (pinfunction "OUT_3") (pintype "bidirectional"))
      (node (ref "X1") (pin "3") (pinfunction "3_3") (pintype "passive"))
    )
    (net (code "57") (name "OUT3") (class "Default")
      (node (ref "U$4") (pin "3") (pinfunction "OUT_3") (pintype "bidirectional"))
      (node (ref "X1") (pin "4") (pinfunction "4_4") (pintype "passive"))
    )
    (net (code "58") (name "OUT4") (class "Default")
      (node (ref "U$5") (pin "3") (pinfunction "OUT_3") (pintype "bidirectional"))
      (node (ref "X1") (pin "5") (pinfunction "5_5") (pintype "passive"))
    )
    (net (code "59") (name "OUT5") (class "Default")
      (node (ref "U$6") (pin "3") (pinfunction "OUT_3") (pintype "bidirectional"))
      (node (ref "X1") (pin "6") (pinfunction "6_6") (pintype "passive"))
    )
    (net (code "60") (name "OUT6") (class "Default")
      (node (ref "U$7") (pin "3") (pinfunction "OUT_3") (pintype "bidirectional"))
      (node (ref "X1") (pin "7") (pinfunction "7_7") (pintype "passive"))
    )
    (net (code "61") (name "OUT7") (class "Default")
      (node (ref "U$8") (pin "3") (pinfunction "OUT_3") (pintype "bidirectional"))
      (node (ref "X1") (pin "8") (pinfunction "8_8") (pintype "passive"))
    )
    (net (code "62") (name "PA0") (class "Default")
      (node (ref "EK-TM4C1294XL") (pin "74") (pinfunction "PA0_74") (pintype "bidirectional"))
      (node (ref "JP3") (pin "4") (pinfunction "4_4") (pintype "passive"))
      (node (ref "JP_EK-TM4C1294XL") (pin "73") (pinfunction "PA0_73") (pintype "bidirectional"))
    )
    (net (code "63") (name "PA1") (class "Default")
      (node (ref "EK-TM4C1294XL") (pin "76") (pinfunction "PA1_76") (pintype "bidirectional"))
      (node (ref "JP4") (pin "4") (pinfunction "4_4") (pintype "passive"))
      (node (ref "JP_EK-TM4C1294XL") (pin "75") (pinfunction "PA1_75") (pintype "bidirectional"))
    )
    (net (code "64") (name "PA2") (class "Default")
      (node (ref "EK-TM4C1294XL") (pin "6") (pinfunction "PA2_6") (pintype "bidirectional"))
      (node (ref "JP5") (pin "4") (pinfunction "4_4") (pintype "passive"))
      (node (ref "JP_EK-TM4C1294XL") (pin "5") (pinfunction "PA2_5") (pintype "bidirectional"))
    )
    (net (code "65") (name "PA3") (class "Default")
      (node (ref "EK-TM4C1294XL") (pin "8") (pinfunction "PA3_8") (pintype "bidirectional"))
      (node (ref "JP6") (pin "4") (pinfunction "4_4") (pintype "passive"))
      (node (ref "JP_EK-TM4C1294XL") (pin "7") (pinfunction "PA3_7") (pintype "bidirectional"))
    )
    (net (code "66") (name "PA4") (class "Default")
      (node (ref "EK-TM4C1294XL") (pin "10") (pinfunction "PA4_10") (pintype "bidirectional"))
      (node (ref "JP1") (pin "2") (pinfunction "2_2") (pintype "passive"))
      (node (ref "JP_EK-TM4C1294XL") (pin "9") (pinfunction "PA4_9") (pintype "bidirectional"))
    )
    (net (code "67") (name "PA5") (class "Default")
      (node (ref "EK-TM4C1294XL") (pin "12") (pinfunction "PA5_12") (pintype "bidirectional"))
      (node (ref "JP2") (pin "2") (pinfunction "2_2") (pintype "passive"))
      (node (ref "JP_EK-TM4C1294XL") (pin "11") (pinfunction "PA5_11") (pintype "bidirectional"))
    )
    (net (code "68") (name "PA6") (class "Default")
      (node (ref "EK-TM4C1294XL") (pin "25") (pinfunction "PA6_25") (pintype "bidirectional"))
      (node (ref "JP7") (pin "2") (pinfunction "2_2") (pintype "passive"))
      (node (ref "JP_EK-TM4C1294XL") (pin "26") (pinfunction "PA6_26") (pintype "bidirectional"))
    )
    (net (code "69") (name "PA7") (class "Default")
      (node (ref "EK-TM4C1294XL") (pin "27") (pinfunction "PA7_27") (pintype "bidirectional"))
      (node (ref "JP8") (pin "2") (pinfunction "2_2") (pintype "passive"))
      (node (ref "JP_EK-TM4C1294XL") (pin "28") (pinfunction "PA7_28") (pintype "bidirectional"))
    )
    (net (code "70") (name "PB0") (class "Default")
      (node (ref "EK-TM4C1294XL") (pin "58") (pinfunction "PB0_58") (pintype "bidirectional"))
      (node (ref "JP_EK-TM4C1294XL") (pin "57") (pinfunction "PB0_57") (pintype "bidirectional"))
    )
    (net (code "71") (name "PB1") (class "Default")
      (node (ref "EK-TM4C1294XL") (pin "60") (pinfunction "PB1_60") (pintype "bidirectional"))
      (node (ref "JP_EK-TM4C1294XL") (pin "59") (pinfunction "PB1_59") (pintype "bidirectional"))
    )
    (net (code "72") (name "PB2") (class "Default")
      (node (ref "EK-TM4C1294XL") (pin "67") (pinfunction "PB2_67") (pintype "bidirectional"))
      (node (ref "JP_EK-TM4C1294XL") (pin "68") (pinfunction "PB2_68") (pintype "bidirectional"))
    )
    (net (code "73") (name "PB3") (class "Default")
      (node (ref "EK-TM4C1294XL") (pin "69") (pinfunction "PB3_69") (pintype "bidirectional"))
      (node (ref "JP_EK-TM4C1294XL") (pin "70") (pinfunction "PB3_70") (pintype "bidirectional"))
    )
    (net (code "74") (name "PB4") (class "Default")
      (node (ref "EK-TM4C1294XL") (pin "5") (pinfunction "PB4_5") (pintype "bidirectional"))
      (node (ref "JP_EK-TM4C1294XL") (pin "6") (pinfunction "PB4_6") (pintype "bidirectional"))
    )
    (net (code "75") (name "PB5") (class "Default")
      (node (ref "EK-TM4C1294XL") (pin "7") (pinfunction "PB5_7") (pintype "bidirectional"))
      (node (ref "JP_EK-TM4C1294XL") (pin "8") (pinfunction "PB5_8") (pintype "bidirectional"))
    )
    (net (code "76") (name "PC4") (class "Default")
      (node (ref "EK-TM4C1294XL") (pin "23") (pinfunction "PC4_23") (pintype "bidirectional"))
      (node (ref "JP_EK-TM4C1294XL") (pin "24") (pinfunction "PC4_24") (pintype "bidirectional"))
    )
    (net (code "77") (name "PC5") (class "Default")
      (node (ref "EK-TM4C1294XL") (pin "21") (pinfunction "PC5_21") (pintype "bidirectional"))
      (node (ref "JP_EK-TM4C1294XL") (pin "22") (pinfunction "PC5_22") (pintype "bidirectional"))
    )
    (net (code "78") (name "PC6") (class "Default")
      (node (ref "EK-TM4C1294XL") (pin "19") (pinfunction "PC6_19") (pintype "bidirectional"))
      (node (ref "JP_EK-TM4C1294XL") (pin "20") (pinfunction "PC6_20") (pintype "bidirectional"))
    )
    (net (code "79") (name "PC7") (class "Default")
      (node (ref "EK-TM4C1294XL") (pin "17") (pinfunction "PC7_17") (pintype "bidirectional"))
      (node (ref "JP_EK-TM4C1294XL") (pin "18") (pinfunction "PC7_18") (pintype "bidirectional"))
    )
    (net (code "80") (name "PD0") (class "Default")
      (node (ref "EK-TM4C1294XL") (pin "50") (pinfunction "PD0_50") (pintype "bidirectional"))
      (node (ref "JP3") (pin "2") (pinfunction "2_2") (pintype "passive"))
      (node (ref "JP_EK-TM4C1294XL") (pin "49") (pinfunction "PD0_49") (pintype "bidirectional"))
    )
    (net (code "81") (name "PD1") (class "Default")
      (node (ref "EK-TM4C1294XL") (pin "48") (pinfunction "PD1_48") (pintype "bidirectional"))
      (node (ref "JP4") (pin "2") (pinfunction "2_2") (pintype "passive"))
      (node (ref "JP_EK-TM4C1294XL") (pin "47") (pinfunction "PD1_47") (pintype "bidirectional"))
    )
    (net (code "82") (name "PD2") (class "Default")
      (node (ref "EK-TM4C1294XL") (pin "52") (pinfunction "PD2_52") (pintype "bidirectional"))
      (node (ref "JP5") (pin "2") (pinfunction "2_2") (pintype "passive"))
      (node (ref "JP_EK-TM4C1294XL") (pin "51") (pinfunction "PD2_51") (pintype "bidirectional"))
    )
    (net (code "83") (name "PD3") (class "Default")
      (node (ref "EK-TM4C1294XL") (pin "46") (pinfunction "PD3_46") (pintype "bidirectional"))
      (node (ref "JP6") (pin "2") (pinfunction "2_2") (pintype "passive"))
      (node (ref "JP_EK-TM4C1294XL") (pin "45") (pinfunction "PD3_45") (pintype "bidirectional"))
    )
    (net (code "84") (name "PD4") (class "Default")
      (node (ref "EK-TM4C1294XL") (pin "40") (pinfunction "PD4_40") (pintype "bidirectional"))
      (node (ref "JP7") (pin "6") (pinfunction "6_6") (pintype "passive"))
      (node (ref "JP_EK-TM4C1294XL") (pin "39") (pinfunction "PD4_39") (pintype "bidirectional"))
    )
    (net (code "85") (name "PD5") (class "Default")
      (node (ref "EK-TM4C1294XL") (pin "38") (pinfunction "PD5_38") (pintype "bidirectional"))
      (node (ref "JP8") (pin "6") (pinfunction "6_6") (pintype "passive"))
      (node (ref "JP_EK-TM4C1294XL") (pin "37") (pinfunction "PD5_37") (pintype "bidirectional"))
    )
    (net (code "86") (name "PD6") (class "Default")
      (node (ref "EK-TM4C1294XL") (pin "44") (pinfunction "PD6_44") (pintype "bidirectional"))
      (node (ref "JP_EK-TM4C1294XL") (pin "43") (pinfunction "PD6_43") (pintype "bidirectional"))
    )
    (net (code "87") (name "PD7") (class "Default")
      (node (ref "EK-TM4C1294XL") (pin "42") (pinfunction "PD7_42") (pintype "bidirectional"))
      (node (ref "JP_EK-TM4C1294XL") (pin "41") (pinfunction "PD7_41") (pintype "bidirectional"))
    )
    (net (code "88") (name "PE0") (class "Default")
      (node (ref "EK-TM4C1294XL") (pin "14") (pinfunction "PE0_14") (pintype "bidirectional"))
      (node (ref "JP_EK-TM4C1294XL") (pin "13") (pinfunction "PE0_13") (pintype "bidirectional"))
    )
    (net (code "89") (name "PE1") (class "Default")
      (node (ref "EK-TM4C1294XL") (pin "16") (pinfunction "PE1_16") (pintype "bidirectional"))
      (node (ref "JP_EK-TM4C1294XL") (pin "15") (pinfunction "PE1_15") (pintype "bidirectional"))
    )
    (net (code "90") (name "PE2") (class "Default")
      (node (ref "EK-TM4C1294XL") (pin "18") (pinfunction "PE2_18") (pintype "bidirectional"))
      (node (ref "JP_EK-TM4C1294XL") (pin "17") (pinfunction "PE2_17") (pintype "bidirectional"))
    )
    (net (code "91") (name "PE3") (class "Default")
      (node (ref "EK-TM4C1294XL") (pin "20") (pinfunction "PE3_20") (pintype "bidirectional"))
      (node (ref "JP_EK-TM4C1294XL") (pin "19") (pinfunction "PE3_19") (pintype "bidirectional"))
    )
    (net (code "92") (name "PE4") (class "Default")
      (node (ref "EK-TM4C1294XL") (pin "22") (pinfunction "PE4_22") (pintype "bidirectional"))
      (node (ref "JP_EK-TM4C1294XL") (pin "21") (pinfunction "PE4_21") (pintype "bidirectional"))
    )
    (net (code "93") (name "PE5") (class "Default")
      (node (ref "EK-TM4C1294XL") (pin "24") (pinfunction "PE5_24") (pintype "bidirectional"))
      (node (ref "JP_EK-TM4C1294XL") (pin "23") (pinfunction "PE5_23") (pintype "bidirectional"))
    )
    (net (code "94") (name "PF0") (class "Default")
      (node (ref "EK-TM4C1294XL") (pin "66") (pinfunction "PF0_66") (pintype "bidirectional"))
      (node (ref "JP_EK-TM4C1294XL") (pin "65") (pinfunction "PF0_65") (pintype "bidirectional"))
    )
    (net (code "95") (name "PF1") (class "Default")
      (node (ref "EK-TM4C1294XL") (pin "68") (pinfunction "PF1_68") (pintype "bidirectional"))
      (node (ref "JP_EK-TM4C1294XL") (pin "67") (pinfunction "PF1_67") (pintype "bidirectional"))
    )
    (net (code "96") (name "PF2") (class "Default")
      (node (ref "EK-TM4C1294XL") (pin "70") (pinfunction "PF2_70") (pintype "bidirectional"))
      (node (ref "JP_EK-TM4C1294XL") (pin "69") (pinfunction "PF2_69") (pintype "bidirectional"))
    )
    (net (code "97") (name "PF3") (class "Default")
      (node (ref "EK-TM4C1294XL") (pin "72") (pinfunction "PF3_72") (pintype "bidirectional"))
      (node (ref "JP_EK-TM4C1294XL") (pin "71") (pinfunction "PF3_71") (pintype "bidirectional"))
    )
    (net (code "98") (name "PF4") (class "Default")
      (node (ref "EK-TM4C1294XL") (pin "64") (pinfunction "PF4_64") (pintype "bidirectional"))
      (node (ref "JP_EK-TM4C1294XL") (pin "63") (pinfunction "PF4_63") (pintype "bidirectional"))
    )
    (net (code "99") (name "PG0") (class "Default")
      (node (ref "EK-TM4C1294XL") (pin "31") (pinfunction "PG0_31") (pintype "bidirectional"))
      (node (ref "JP_EK-TM4C1294XL") (pin "32") (pinfunction "PG0_32") (pintype "bidirectional"))
    )
    (net (code "100") (name "PG1") (class "Default")
      (node (ref "EK-TM4C1294XL") (pin "29") (pinfunction "PG1_29") (pintype "bidirectional"))
      (node (ref "JP_EK-TM4C1294XL") (pin "30") (pinfunction "PG1_30") (pintype "bidirectional"))
    )
    (net (code "101") (name "PH0") (class "Default")
      (node (ref "EK-TM4C1294XL") (pin "9") (pinfunction "PH0_9") (pintype "bidirectional"))
      (node (ref "JP_EK-TM4C1294XL") (pin "10") (pinfunction "PH0_10") (pintype "bidirectional"))
    )
    (net (code "102") (name "PH1") (class "Default")
      (node (ref "EK-TM4C1294XL") (pin "11") (pinfunction "PH1_11") (pintype "bidirectional"))
      (node (ref "JP_EK-TM4C1294XL") (pin "12") (pinfunction "PH1_12") (pintype "bidirectional"))
    )
    (net (code "103") (name "PH2") (class "Default")
      (node (ref "EK-TM4C1294XL") (pin "13") (pinfunction "PH2_13") (pintype "bidirectional"))
      (node (ref "JP_EK-TM4C1294XL") (pin "14") (pinfunction "PH2_14") (pintype "bidirectional"))
    )
    (net (code "104") (name "PH3") (class "Default")
      (node (ref "EK-TM4C1294XL") (pin "15") (pinfunction "PH3_15") (pintype "bidirectional"))
      (node (ref "JP_EK-TM4C1294XL") (pin "16") (pinfunction "PH3_16") (pintype "bidirectional"))
    )
    (net (code "105") (name "PJ0") (class "Default")
      (node (ref "EK-TM4C1294XL") (pin "82") (pinfunction "PJ0_82") (pintype "bidirectional"))
      (node (ref "JP_EK-TM4C1294XL") (pin "81") (pinfunction "PJ0_81") (pintype "bidirectional"))
    )
    (net (code "106") (name "PJ1") (class "Default")
      (node (ref "EK-TM4C1294XL") (pin "84") (pinfunction "PJ1_84") (pintype "bidirectional"))
      (node (ref "JP_EK-TM4C1294XL") (pin "83") (pinfunction "PJ1_83") (pintype "bidirectional"))
    )
    (net (code "107") (name "PK0") (class "Default")
      (node (ref "EK-TM4C1294XL") (pin "26") (pinfunction "PK0_26") (pintype "bidirectional"))
      (node (ref "JP9") (pin "2") (pinfunction "2_2") (pintype "passive"))
      (node (ref "JP_EK-TM4C1294XL") (pin "25") (pinfunction "PK0_25") (pintype "bidirectional"))
    )
    (net (code "108") (name "PK1") (class "Default")
      (node (ref "EK-TM4C1294XL") (pin "28") (pinfunction "PK1_28") (pintype "bidirectional"))
      (node (ref "JP10") (pin "2") (pinfunction "2_2") (pintype "passive"))
      (node (ref "JP_EK-TM4C1294XL") (pin "27") (pinfunction "PK1_27") (pintype "bidirectional"))
    )
    (net (code "109") (name "PK2") (class "Default")
      (node (ref "EK-TM4C1294XL") (pin "30") (pinfunction "PK2_30") (pintype "bidirectional"))
      (node (ref "JP11") (pin "2") (pinfunction "2_2") (pintype "passive"))
      (node (ref "JP_EK-TM4C1294XL") (pin "29") (pinfunction "PK2_29") (pintype "bidirectional"))
    )
    (net (code "110") (name "PK3") (class "Default")
      (node (ref "EK-TM4C1294XL") (pin "32") (pinfunction "PK3_32") (pintype "bidirectional"))
      (node (ref "JP12") (pin "2") (pinfunction "2_2") (pintype "passive"))
      (node (ref "JP_EK-TM4C1294XL") (pin "31") (pinfunction "PK3_31") (pintype "bidirectional"))
    )
    (net (code "111") (name "PK4") (class "Default")
      (node (ref "EK-TM4C1294XL") (pin "77") (pinfunction "PK4_77") (pintype "bidirectional"))
      (node (ref "JP_EK-TM4C1294XL") (pin "78") (pinfunction "PK4_78") (pintype "bidirectional"))
    )
    (net (code "112") (name "PK5") (class "Default")
      (node (ref "EK-TM4C1294XL") (pin "75") (pinfunction "PK5_75") (pintype "bidirectional"))
      (node (ref "JP_EK-TM4C1294XL") (pin "76") (pinfunction "PK5_76") (pintype "bidirectional"))
    )
    (net (code "113") (name "PK6") (class "Default")
      (node (ref "EK-TM4C1294XL") (pin "63") (pinfunction "PK6_63") (pintype "bidirectional"))
      (node (ref "JP_EK-TM4C1294XL") (pin "64") (pinfunction "PK6_64") (pintype "bidirectional"))
    )
    (net (code "114") (name "PK7") (class "Default")
      (node (ref "EK-TM4C1294XL") (pin "59") (pinfunction "PK7_59") (pintype "bidirectional"))
      (node (ref "JP_EK-TM4C1294XL") (pin "60") (pinfunction "PK7_60") (pintype "bidirectional"))
    )
    (net (code "115") (name "PL0") (class "Default")
      (node (ref "EK-TM4C1294XL") (pin "43") (pinfunction "PL0_43") (pintype "bidirectional"))
      (node (ref "JP_EK-TM4C1294XL") (pin "44") (pinfunction "PL0_44") (pintype "bidirectional"))
    )
    (net (code "116") (name "PL1") (class "Default")
      (node (ref "EK-TM4C1294XL") (pin "45") (pinfunction "PL1_45") (pintype "bidirectional"))
      (node (ref "JP_EK-TM4C1294XL") (pin "46") (pinfunction "PL1_46") (pintype "bidirectional"))
    )
    (net (code "117") (name "PL2") (class "Default")
      (node (ref "EK-TM4C1294XL") (pin "47") (pinfunction "PL2_47") (pintype "bidirectional"))
      (node (ref "JP_EK-TM4C1294XL") (pin "48") (pinfunction "PL2_48") (pintype "bidirectional"))
    )
    (net (code "118") (name "PL3") (class "Default")
      (node (ref "EK-TM4C1294XL") (pin "49") (pinfunction "PL3_49") (pintype "bidirectional"))
      (node (ref "JP_EK-TM4C1294XL") (pin "50") (pinfunction "PL3_50") (pintype "bidirectional"))
    )
    (net (code "119") (name "PL4") (class "Default")
      (node (ref "EK-TM4C1294XL") (pin "65") (pinfunction "PL4_65") (pintype "bidirectional"))
      (node (ref "JP3") (pin "6") (pinfunction "6_6") (pintype "passive"))
      (node (ref "JP_EK-TM4C1294XL") (pin "66") (pinfunction "PL4_66") (pintype "bidirectional"))
    )
    (net (code "120") (name "PL5") (class "Default")
      (node (ref "EK-TM4C1294XL") (pin "79") (pinfunction "PL5_79") (pintype "bidirectional"))
      (node (ref "JP4") (pin "6") (pinfunction "6_6") (pintype "passive"))
      (node (ref "JP_EK-TM4C1294XL") (pin "80") (pinfunction "PL5_80") (pintype "bidirectional"))
    )
    (net (code "121") (name "PL6") (class "Default")
      (node (ref "JP5") (pin "6") (pinfunction "6_6") (pintype "passive"))
    )
    (net (code "122") (name "PL7") (class "Default")
      (node (ref "JP6") (pin "6") (pinfunction "6_6") (pintype "passive"))
    )
    (net (code "123") (name "PM0") (class "Default")
      (node (ref "EK-TM4C1294XL") (pin "41") (pinfunction "PM0_41") (pintype "bidirectional"))
      (node (ref "JP1") (pin "4") (pinfunction "4_4") (pintype "passive"))
      (node (ref "JP_EK-TM4C1294XL") (pin "42") (pinfunction "PM0_42") (pintype "bidirectional"))
    )
    (net (code "124") (name "PM1") (class "Default")
      (node (ref "EK-TM4C1294XL") (pin "39") (pinfunction "PM1_39") (pintype "bidirectional"))
      (node (ref "JP2") (pin "4") (pinfunction "4_4") (pintype "passive"))
      (node (ref "JP_EK-TM4C1294XL") (pin "40") (pinfunction "PM1_40") (pintype "bidirectional"))
    )
    (net (code "125") (name "PM2") (class "Default")
      (node (ref "EK-TM4C1294XL") (pin "37") (pinfunction "PM2_37") (pintype "bidirectional"))
      (node (ref "JP7") (pin "4") (pinfunction "4_4") (pintype "passive"))
      (node (ref "JP_EK-TM4C1294XL") (pin "38") (pinfunction "PM2_38") (pintype "bidirectional"))
    )
    (net (code "126") (name "PM3") (class "Default")
      (node (ref "EK-TM4C1294XL") (pin "33") (pinfunction "PM3_33") (pintype "bidirectional"))
      (node (ref "JP8") (pin "4") (pinfunction "4_4") (pintype "passive"))
      (node (ref "JP_EK-TM4C1294XL") (pin "34") (pinfunction "PM3_34") (pintype "bidirectional"))
    )
    (net (code "127") (name "PM4") (class "Default")
      (node (ref "EK-TM4C1294XL") (pin "92") (pinfunction "PM4_92") (pintype "bidirectional"))
      (node (ref "JP16") (pin "2") (pinfunction "2_2") (pintype "passive"))
      (node (ref "JP_EK-TM4C1294XL") (pin "91") (pinfunction "PM4_91") (pintype "bidirectional"))
    )
    (net (code "128") (name "PM5") (class "Default")
      (node (ref "EK-TM4C1294XL") (pin "90") (pinfunction "PM5_90") (pintype "bidirectional"))
      (node (ref "JP15") (pin "2") (pinfunction "2_2") (pintype "passive"))
      (node (ref "JP_EK-TM4C1294XL") (pin "89") (pinfunction "PM5_89") (pintype "bidirectional"))
    )
    (net (code "129") (name "PM6") (class "Default")
      (node (ref "EK-TM4C1294XL") (pin "88") (pinfunction "PM6_88") (pintype "bidirectional"))
      (node (ref "JP14") (pin "2") (pinfunction "2_2") (pintype "passive"))
      (node (ref "JP_EK-TM4C1294XL") (pin "87") (pinfunction "PM6_87") (pintype "bidirectional"))
    )
    (net (code "130") (name "PM7") (class "Default")
      (node (ref "EK-TM4C1294XL") (pin "86") (pinfunction "PM7_86") (pintype "bidirectional"))
      (node (ref "JP13") (pin "2") (pinfunction "2_2") (pintype "passive"))
      (node (ref "JP_EK-TM4C1294XL") (pin "85") (pinfunction "PM7_85") (pintype "bidirectional"))
    )
    (net (code "131") (name "PN0") (class "Default")
      (node (ref "EK-TM4C1294XL") (pin "85") (pinfunction "PN0_85") (pintype "bidirectional"))
      (node (ref "JP_EK-TM4C1294XL") (pin "86") (pinfunction "PN0_86") (pintype "bidirectional"))
    )
    (net (code "132") (name "PN1") (class "Default")
      (node (ref "EK-TM4C1294XL") (pin "87") (pinfunction "PN1_87") (pintype "bidirectional"))
      (node (ref "JP_EK-TM4C1294XL") (pin "88") (pinfunction "PN1_88") (pintype "bidirectional"))
    )
    (net (code "133") (name "PN2") (class "Default")
      (node (ref "EK-TM4C1294XL") (pin "89") (pinfunction "PN2_89") (pintype "bidirectional"))
      (node (ref "JP_EK-TM4C1294XL") (pin "90") (pinfunction "PN2_90") (pintype "bidirectional"))
    )
    (net (code "134") (name "PN3") (class "Default")
      (node (ref "EK-TM4C1294XL") (pin "91") (pinfunction "PN3_91") (pintype "bidirectional"))
      (node (ref "JP_EK-TM4C1294XL") (pin "92") (pinfunction "PN3_92") (pintype "bidirectional"))
    )
    (net (code "135") (name "PN4") (class "Default")
      (node (ref "EK-TM4C1294XL") (pin "81") (pinfunction "PN4_81") (pintype "bidirectional"))
      (node (ref "JP_EK-TM4C1294XL") (pin "82") (pinfunction "PN4_82") (pintype "bidirectional"))
    )
    (net (code "136") (name "PN5") (class "Default")
      (node (ref "EK-TM4C1294XL") (pin "83") (pinfunction "PN5_83") (pintype "bidirectional"))
      (node (ref "JP_EK-TM4C1294XL") (pin "84") (pinfunction "PN5_84") (pintype "bidirectional"))
    )
    (net (code "137") (name "PP0") (class "Default")
      (node (ref "EK-TM4C1294XL") (pin "54") (pinfunction "PP0_54") (pintype "bidirectional"))
      (node (ref "JP_EK-TM4C1294XL") (pin "53") (pinfunction "PP0_53") (pintype "bidirectional"))
    )
    (net (code "138") (name "PP1") (class "Default")
      (node (ref "EK-TM4C1294XL") (pin "56") (pinfunction "PP1_56") (pintype "bidirectional"))
      (node (ref "JP_EK-TM4C1294XL") (pin "55") (pinfunction "PP1_55") (pintype "bidirectional"))
    )
    (net (code "139") (name "PP2") (class "Default")
      (node (ref "EK-TM4C1294XL") (pin "71") (pinfunction "PP2_71") (pintype "bidirectional"))
      (node (ref "JP_EK-TM4C1294XL") (pin "72") (pinfunction "PP2_72") (pintype "bidirectional"))
    )
    (net (code "140") (name "PP3") (class "Default")
      (node (ref "EK-TM4C1294XL") (pin "73") (pinfunction "PP3_73") (pintype "bidirectional"))
      (node (ref "JP_EK-TM4C1294XL") (pin "74") (pinfunction "PP3_74") (pintype "bidirectional"))
    )
    (net (code "141") (name "PP4") (class "Default")
      (node (ref "EK-TM4C1294XL") (pin "78") (pinfunction "PP4_78") (pintype "bidirectional"))
      (node (ref "JP_EK-TM4C1294XL") (pin "77") (pinfunction "PP4_77") (pintype "bidirectional"))
    )
    (net (code "142") (name "PP5") (class "Default")
      (node (ref "EK-TM4C1294XL") (pin "80") (pinfunction "PP5_80") (pintype "bidirectional"))
      (node (ref "JP_EK-TM4C1294XL") (pin "79") (pinfunction "PP5_79") (pintype "bidirectional"))
    )
    (net (code "143") (name "PQ0") (class "Default")
      (node (ref "EK-TM4C1294XL") (pin "51") (pinfunction "PQ0_51") (pintype "bidirectional"))
      (node (ref "JP_EK-TM4C1294XL") (pin "52") (pinfunction "PQ0_52") (pintype "bidirectional"))
    )
    (net (code "144") (name "PQ1") (class "Default")
      (node (ref "EK-TM4C1294XL") (pin "53") (pinfunction "PQ1_53") (pintype "bidirectional"))
      (node (ref "JP_EK-TM4C1294XL") (pin "54") (pinfunction "PQ1_54") (pintype "bidirectional"))
    )
    (net (code "145") (name "PQ2") (class "Default")
      (node (ref "EK-TM4C1294XL") (pin "55") (pinfunction "PQ2_55") (pintype "bidirectional"))
      (node (ref "JP_EK-TM4C1294XL") (pin "56") (pinfunction "PQ2_56") (pintype "bidirectional"))
    )
    (net (code "146") (name "PQ3") (class "Default")
      (node (ref "EK-TM4C1294XL") (pin "57") (pinfunction "PQ3_57") (pintype "bidirectional"))
      (node (ref "JP_EK-TM4C1294XL") (pin "58") (pinfunction "PQ3_58") (pintype "bidirectional"))
    )
    (net (code "147") (name "PQ4") (class "Default")
      (node (ref "EK-TM4C1294XL") (pin "93") (pinfunction "PQ4_93") (pintype "bidirectional"))
      (node (ref "JP_EK-TM4C1294XL") (pin "94") (pinfunction "PQ4_94") (pintype "bidirectional"))
    )
    (net (code "148") (name "RESET") (class "Default")
      (node (ref "EK-TM4C1294XL") (pin "94") (pinfunction "RESET_94") (pintype "bidirectional"))
      (node (ref "JP_EK-TM4C1294XL") (pin "93") (pinfunction "RESET_93") (pintype "bidirectional"))
    )
    (net (code "149") (name "SUP_D0D3") (class "Default")
      (node (ref "JP17") (pin "1") (pinfunction "1_1") (pintype "passive"))
      (node (ref "JP17") (pin "3") (pinfunction "3_3") (pintype "passive"))
      (node (ref "JP17") (pin "5") (pinfunction "5_5") (pintype "passive"))
      (node (ref "JP17") (pin "7") (pinfunction "7_7") (pintype "passive"))
      (node (ref "U$1") (pin "5") (pinfunction "VBB2_5") (pintype "bidirectional"))
      (node (ref "U$1") (pin "6") (pinfunction "VBB3_6") (pintype "bidirectional"))
      (node (ref "U$1") (pin "7") (pinfunction "VBB4_7") (pintype "bidirectional"))
      (node (ref "U$1") (pin "8") (pinfunction "VBB_8") (pintype "bidirectional"))
      (node (ref "U$2") (pin "5") (pinfunction "VBB2_5") (pintype "bidirectional"))
      (node (ref "U$2") (pin "6") (pinfunction "VBB3_6") (pintype "bidirectional"))
      (node (ref "U$2") (pin "7") (pinfunction "VBB4_7") (pintype "bidirectional"))
      (node (ref "U$2") (pin "8") (pinfunction "VBB_8") (pintype "bidirectional"))
      (node (ref "U$3") (pin "5") (pinfunction "VBB2_5") (pintype "bidirectional"))
      (node (ref "U$3") (pin "6") (pinfunction "VBB3_6") (pintype "bidirectional"))
      (node (ref "U$3") (pin "7") (pinfunction "VBB4_7") (pintype "bidirectional"))
      (node (ref "U$3") (pin "8") (pinfunction "VBB_8") (pintype "bidirectional"))
      (node (ref "U$4") (pin "5") (pinfunction "VBB2_5") (pintype "bidirectional"))
      (node (ref "U$4") (pin "6") (pinfunction "VBB3_6") (pintype "bidirectional"))
      (node (ref "U$4") (pin "7") (pinfunction "VBB4_7") (pintype "bidirectional"))
      (node (ref "U$4") (pin "8") (pinfunction "VBB_8") (pintype "bidirectional"))
    )
    (net (code "150") (name "SUP_D4D7") (class "Default")
      (node (ref "JP18") (pin "1") (pinfunction "1_1") (pintype "passive"))
      (node (ref "JP18") (pin "3") (pinfunction "3_3") (pintype "passive"))
      (node (ref "JP18") (pin "5") (pinfunction "5_5") (pintype "passive"))
      (node (ref "JP18") (pin "7") (pinfunction "7_7") (pintype "passive"))
      (node (ref "U$5") (pin "5") (pinfunction "VBB2_5") (pintype "bidirectional"))
      (node (ref "U$5") (pin "6") (pinfunction "VBB3_6") (pintype "bidirectional"))
      (node (ref "U$5") (pin "7") (pinfunction "VBB4_7") (pintype "bidirectional"))
      (node (ref "U$5") (pin "8") (pinfunction "VBB_8") (pintype "bidirectional"))
      (node (ref "U$6") (pin "5") (pinfunction "VBB2_5") (pintype "bidirectional"))
      (node (ref "U$6") (pin "6") (pinfunction "VBB3_6") (pintype "bidirectional"))
      (node (ref "U$6") (pin "7") (pinfunction "VBB4_7") (pintype "bidirectional"))
      (node (ref "U$6") (pin "8") (pinfunction "VBB_8") (pintype "bidirectional"))
      (node (ref "U$7") (pin "5") (pinfunction "VBB2_5") (pintype "bidirectional"))
      (node (ref "U$7") (pin "6") (pinfunction "VBB3_6") (pintype "bidirectional"))
      (node (ref "U$7") (pin "7") (pinfunction "VBB4_7") (pintype "bidirectional"))
      (node (ref "U$7") (pin "8") (pinfunction "VBB_8") (pintype "bidirectional"))
      (node (ref "U$8") (pin "5") (pinfunction "VBB2_5") (pintype "bidirectional"))
      (node (ref "U$8") (pin "6") (pinfunction "VBB3_6") (pintype "bidirectional"))
      (node (ref "U$8") (pin "7") (pinfunction "VBB4_7") (pintype "bidirectional"))
      (node (ref "U$8") (pin "8") (pinfunction "VBB_8") (pintype "bidirectional"))
    )
    (net (code "151") (name "SUP_EXT1") (class "Default")
      (node (ref "JP17") (pin "8") (pinfunction "8_8") (pintype "passive"))
      (node (ref "X1") (pin "10") (pinfunction "10_10") (pintype "passive"))
    )
    (net (code "152") (name "SUP_EXT2") (class "Default")
      (node (ref "JP18") (pin "8") (pinfunction "8_8") (pintype "passive"))
      (node (ref "X1") (pin "18") (pinfunction "18_18") (pintype "passive"))
    )
    (net (code "153") (name "T0CCP0") (class "Default")
      (node (ref "D7") (pin "3") (pinfunction "C1A2_3") (pintype "passive"))
      (node (ref "JP3") (pin "1") (pinfunction "1_1") (pintype "passive"))
      (node (ref "JP3") (pin "3") (pinfunction "3_3") (pintype "passive"))
      (node (ref "JP3") (pin "5") (pinfunction "5_5") (pintype "passive"))
      (node (ref "R20") (pin "2") (pinfunction "2_2") (pintype "passive"))
      (node (ref "R24") (pin "1") (pinfunction "1_1") (pintype "passive"))
      (node (ref "SJ1") (pin "2") (pinfunction "2_2") (pintype "passive"))
    )
    (net (code "154") (name "T0CCP1") (class "Default")
      (node (ref "D1") (pin "3") (pinfunction "C1A2_3") (pintype "passive"))
      (node (ref "JP4") (pin "1") (pinfunction "1_1") (pintype "passive"))
      (node (ref "JP4") (pin "3") (pinfunction "3_3") (pintype "passive"))
      (node (ref "JP4") (pin "5") (pinfunction "5_5") (pintype "passive"))
      (node (ref "R2") (pin "2") (pinfunction "2_2") (pintype "passive"))
      (node (ref "R6") (pin "1") (pinfunction "1_1") (pintype "passive"))
      (node (ref "SJ2") (pin "2") (pinfunction "2_2") (pintype "passive"))
    )
    (net (code "155") (name "T1CCP0") (class "Default")
      (node (ref "D3") (pin "3") (pinfunction "C1A2_3") (pintype "passive"))
      (node (ref "JP5") (pin "1") (pinfunction "1_1") (pintype "passive"))
      (node (ref "JP5") (pin "3") (pinfunction "3_3") (pintype "passive"))
      (node (ref "JP5") (pin "5") (pinfunction "5_5") (pintype "passive"))
      (node (ref "R12") (pin "1") (pinfunction "1_1") (pintype "passive"))
      (node (ref "R8") (pin "2") (pinfunction "2_2") (pintype "passive"))
      (node (ref "SJ3") (pin "2") (pinfunction "2_2") (pintype "passive"))
    )
    (net (code "156") (name "T1CCP1") (class "Default")
      (node (ref "D5") (pin "3") (pinfunction "C1A2_3") (pintype "passive"))
      (node (ref "JP6") (pin "1") (pinfunction "1_1") (pintype "passive"))
      (node (ref "JP6") (pin "3") (pinfunction "3_3") (pintype "passive"))
      (node (ref "JP6") (pin "5") (pinfunction "5_5") (pintype "passive"))
      (node (ref "R14") (pin "2") (pinfunction "2_2") (pintype "passive"))
      (node (ref "R18") (pin "1") (pinfunction "1_1") (pintype "passive"))
      (node (ref "SJ4") (pin "2") (pinfunction "2_2") (pintype "passive"))
    )
    (net (code "157") (name "T2CCP0") (class "Default")
      (node (ref "D9") (pin "3") (pinfunction "C1A2_3") (pintype "passive"))
      (node (ref "JP1") (pin "1") (pinfunction "1_1") (pintype "passive"))
      (node (ref "JP1") (pin "3") (pinfunction "3_3") (pintype "passive"))
      (node (ref "R26") (pin "2") (pinfunction "2_2") (pintype "passive"))
      (node (ref "R30") (pin "1") (pinfunction "1_1") (pintype "passive"))
      (node (ref "SJ5") (pin "2") (pinfunction "2_2") (pintype "passive"))
    )
    (net (code "158") (name "T2CCP1") (class "Default")
      (node (ref "D11") (pin "3") (pinfunction "C1A2_3") (pintype "passive"))
      (node (ref "JP2") (pin "1") (pinfunction "1_1") (pintype "passive"))
      (node (ref "JP2") (pin "3") (pinfunction "3_3") (pintype "passive"))
      (node (ref "R32") (pin "2") (pinfunction "2_2") (pintype "passive"))
      (node (ref "R36") (pin "1") (pinfunction "1_1") (pintype "passive"))
      (node (ref "SJ6") (pin "2") (pinfunction "2_2") (pintype "passive"))
    )
    (net (code "159") (name "T3CCP0") (class "Default")
      (node (ref "D13") (pin "3") (pinfunction "C1A2_3") (pintype "passive"))
      (node (ref "JP7") (pin "1") (pinfunction "1_1") (pintype "passive"))
      (node (ref "JP7") (pin "3") (pinfunction "3_3") (pintype "passive"))
      (node (ref "JP7") (pin "5") (pinfunction "5_5") (pintype "passive"))
      (node (ref "R38") (pin "2") (pinfunction "2_2") (pintype "passive"))
      (node (ref "R42") (pin "1") (pinfunction "1_1") (pintype "passive"))
      (node (ref "SJ7") (pin "2") (pinfunction "2_2") (pintype "passive"))
    )
    (net (code "160") (name "T3CCP1") (class "Default")
      (node (ref "D15") (pin "3") (pinfunction "C1A2_3") (pintype "passive"))
      (node (ref "JP8") (pin "1") (pinfunction "1_1") (pintype "passive"))
      (node (ref "JP8") (pin "3") (pinfunction "3_3") (pintype "passive"))
      (node (ref "JP8") (pin "5") (pinfunction "5_5") (pintype "passive"))
      (node (ref "R44") (pin "2") (pinfunction "2_2") (pintype "passive"))
      (node (ref "R48") (pin "1") (pinfunction "1_1") (pintype "passive"))
      (node (ref "SJ8") (pin "2") (pinfunction "2_2") (pintype "passive"))
    )
    (net (code "161") (name "VREF") (class "Default")
      (node (ref "EK-TM4C1294XL") (pin "34") (pinfunction "VREF_34") (pintype "input"))
      (node (ref "JP_EK-TM4C1294XL") (pin "33") (pinfunction "VREF_33") (pintype "input"))
    )
    (net (code "162") (name "WAKE") (class "Default")
      (node (ref "EK-TM4C1294XL") (pin "95") (pinfunction "WAKE_95") (pintype "bidirectional"))
      (node (ref "JP_EK-TM4C1294XL") (pin "96") (pinfunction "WAKE_96") (pintype "bidirectional"))
    )
    (net (code "163") (name "unconnected-(U$1-ST-Pad4)") (class "Default")
      (node (ref "U$1") (pin "4") (pinfunction "ST_4") (pintype "bidirectional"))
    )
    (net (code "164") (name "unconnected-(U$2-ST-Pad4)") (class "Default")
      (node (ref "U$2") (pin "4") (pinfunction "ST_4") (pintype "bidirectional"))
    )
    (net (code "165") (name "unconnected-(U$3-ST-Pad4)") (class "Default")
      (node (ref "U$3") (pin "4") (pinfunction "ST_4") (pintype "bidirectional"))
    )
    (net (code "166") (name "unconnected-(U$4-ST-Pad4)") (class "Default")
      (node (ref "U$4") (pin "4") (pinfunction "ST_4") (pintype "bidirectional"))
    )
    (net (code "167") (name "unconnected-(U$5-ST-Pad4)") (class "Default")
      (node (ref "U$5") (pin "4") (pinfunction "ST_4") (pintype "bidirectional"))
    )
    (net (code "168") (name "unconnected-(U$6-ST-Pad4)") (class "Default")
      (node (ref "U$6") (pin "4") (pinfunction "ST_4") (pintype "bidirectional"))
    )
    (net (code "169") (name "unconnected-(U$7-ST-Pad4)") (class "Default")
      (node (ref "U$7") (pin "4") (pinfunction "ST_4") (pintype "bidirectional"))
    )
    (net (code "170") (name "unconnected-(U$8-ST-Pad4)") (class "Default")
      (node (ref "U$8") (pin "4") (pinfunction "ST_4") (pintype "bidirectional"))
    )
  )
)
